# Control_board_FINAL.net
KiCad netlist of a schematic drawn in EAGLE
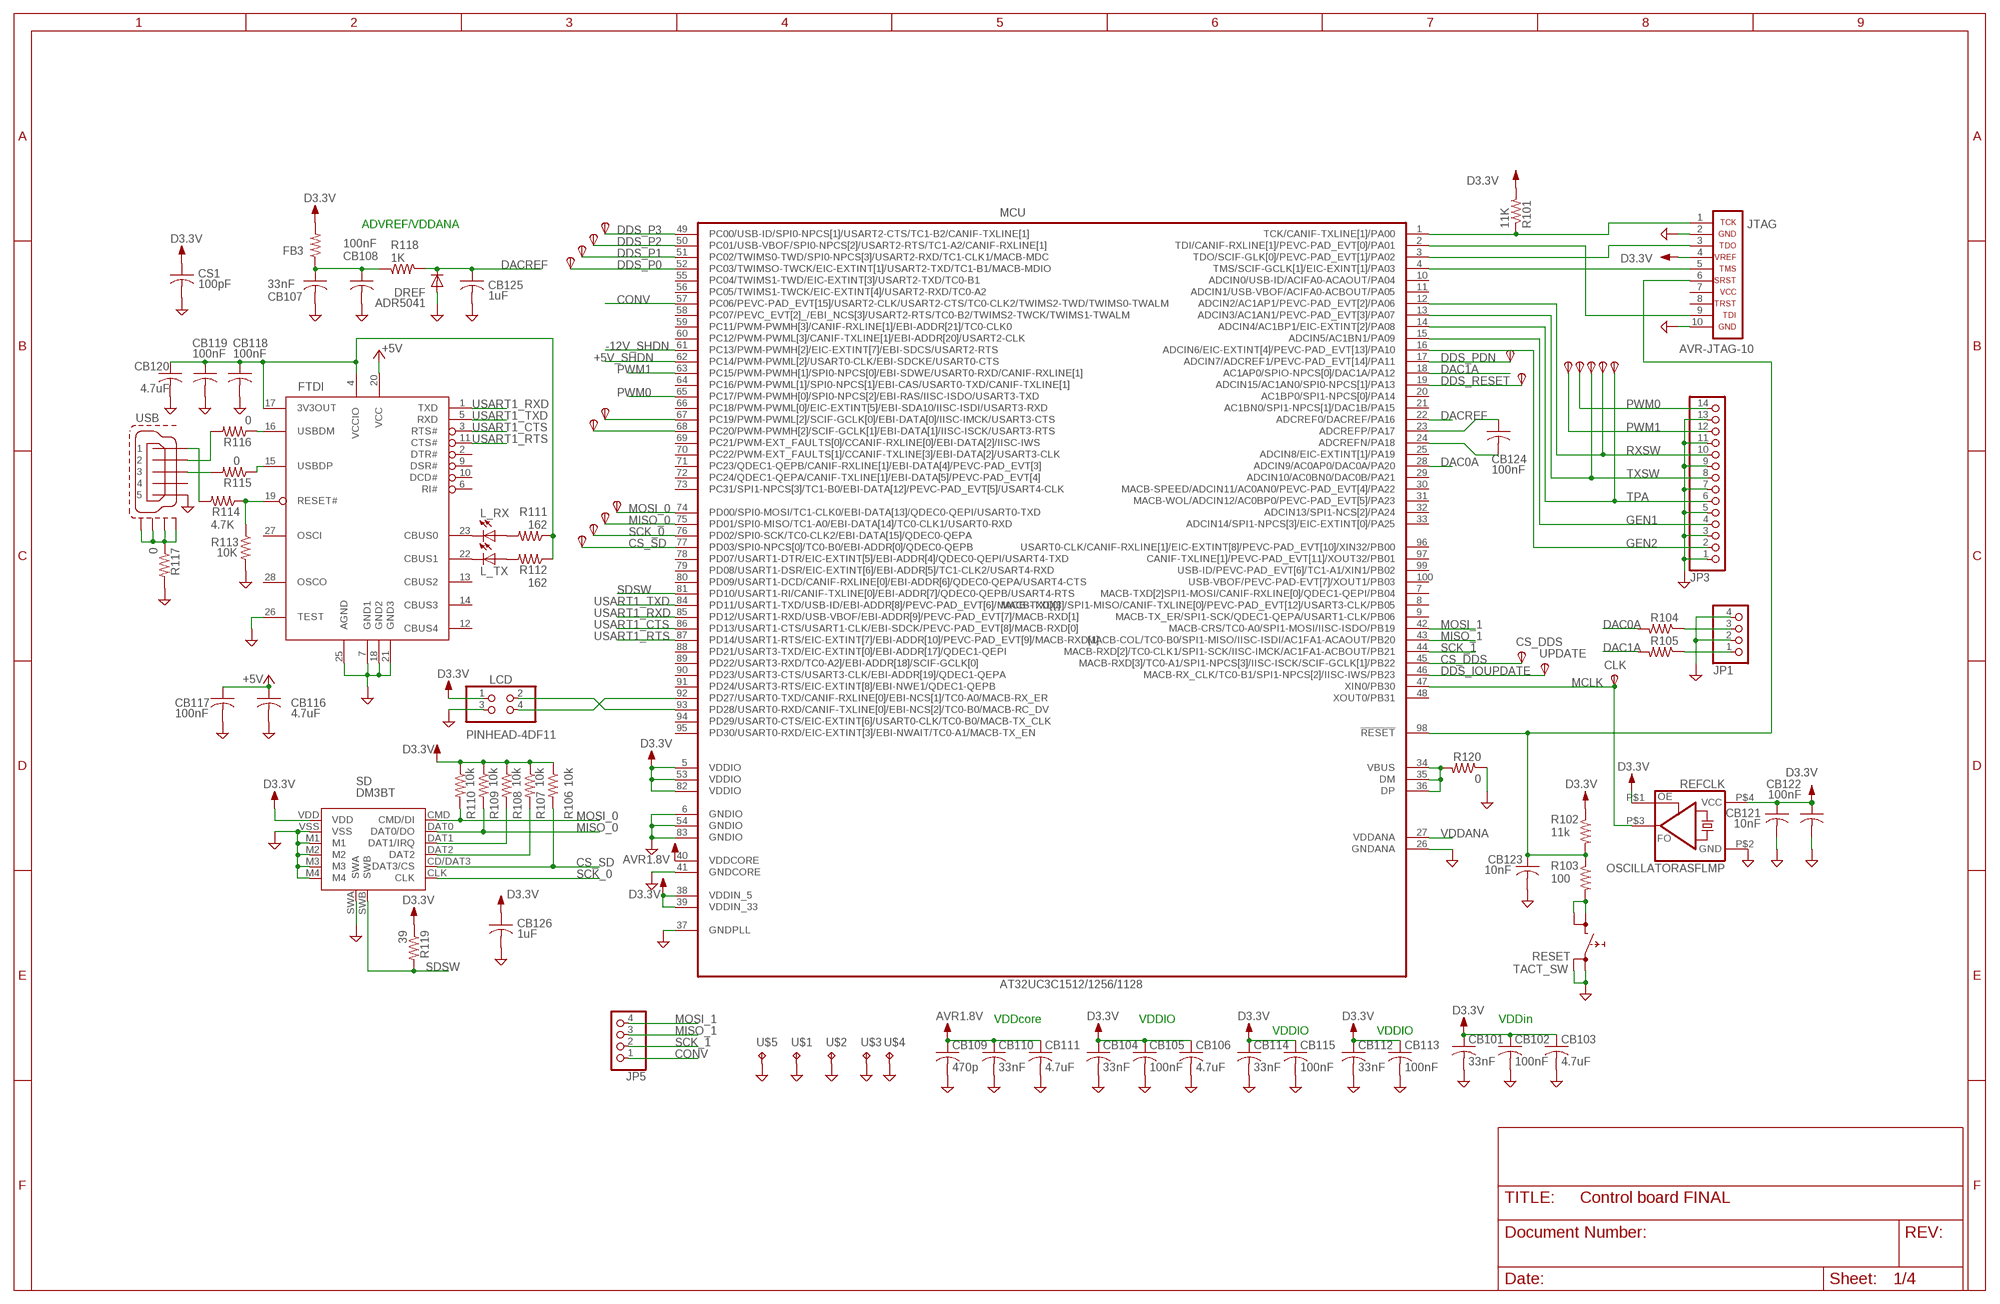
[diagram p0: schematic, sheet 1]
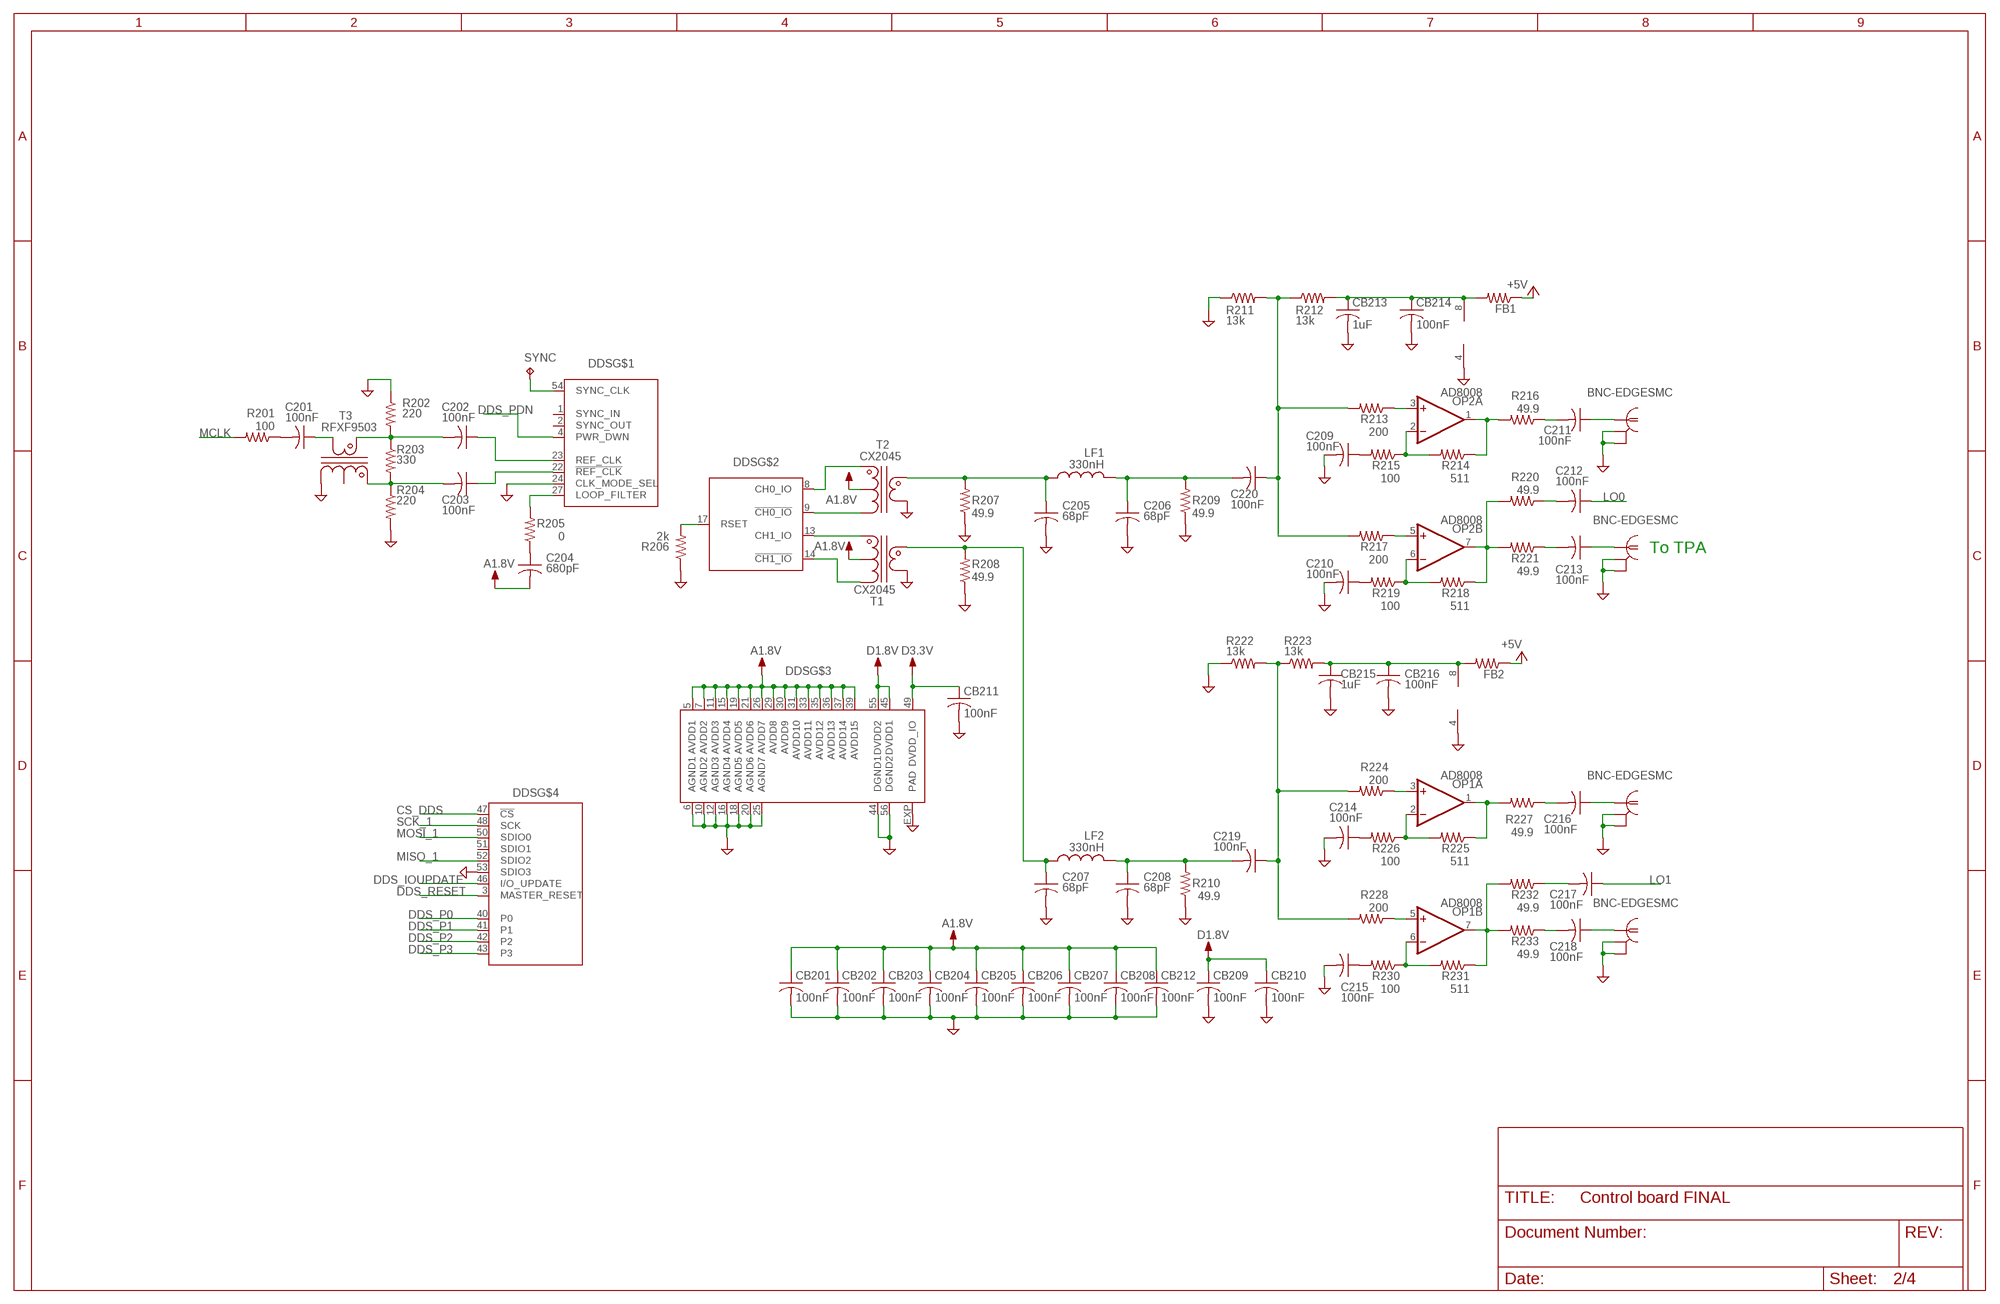
[diagram p1: schematic, sheet 2]
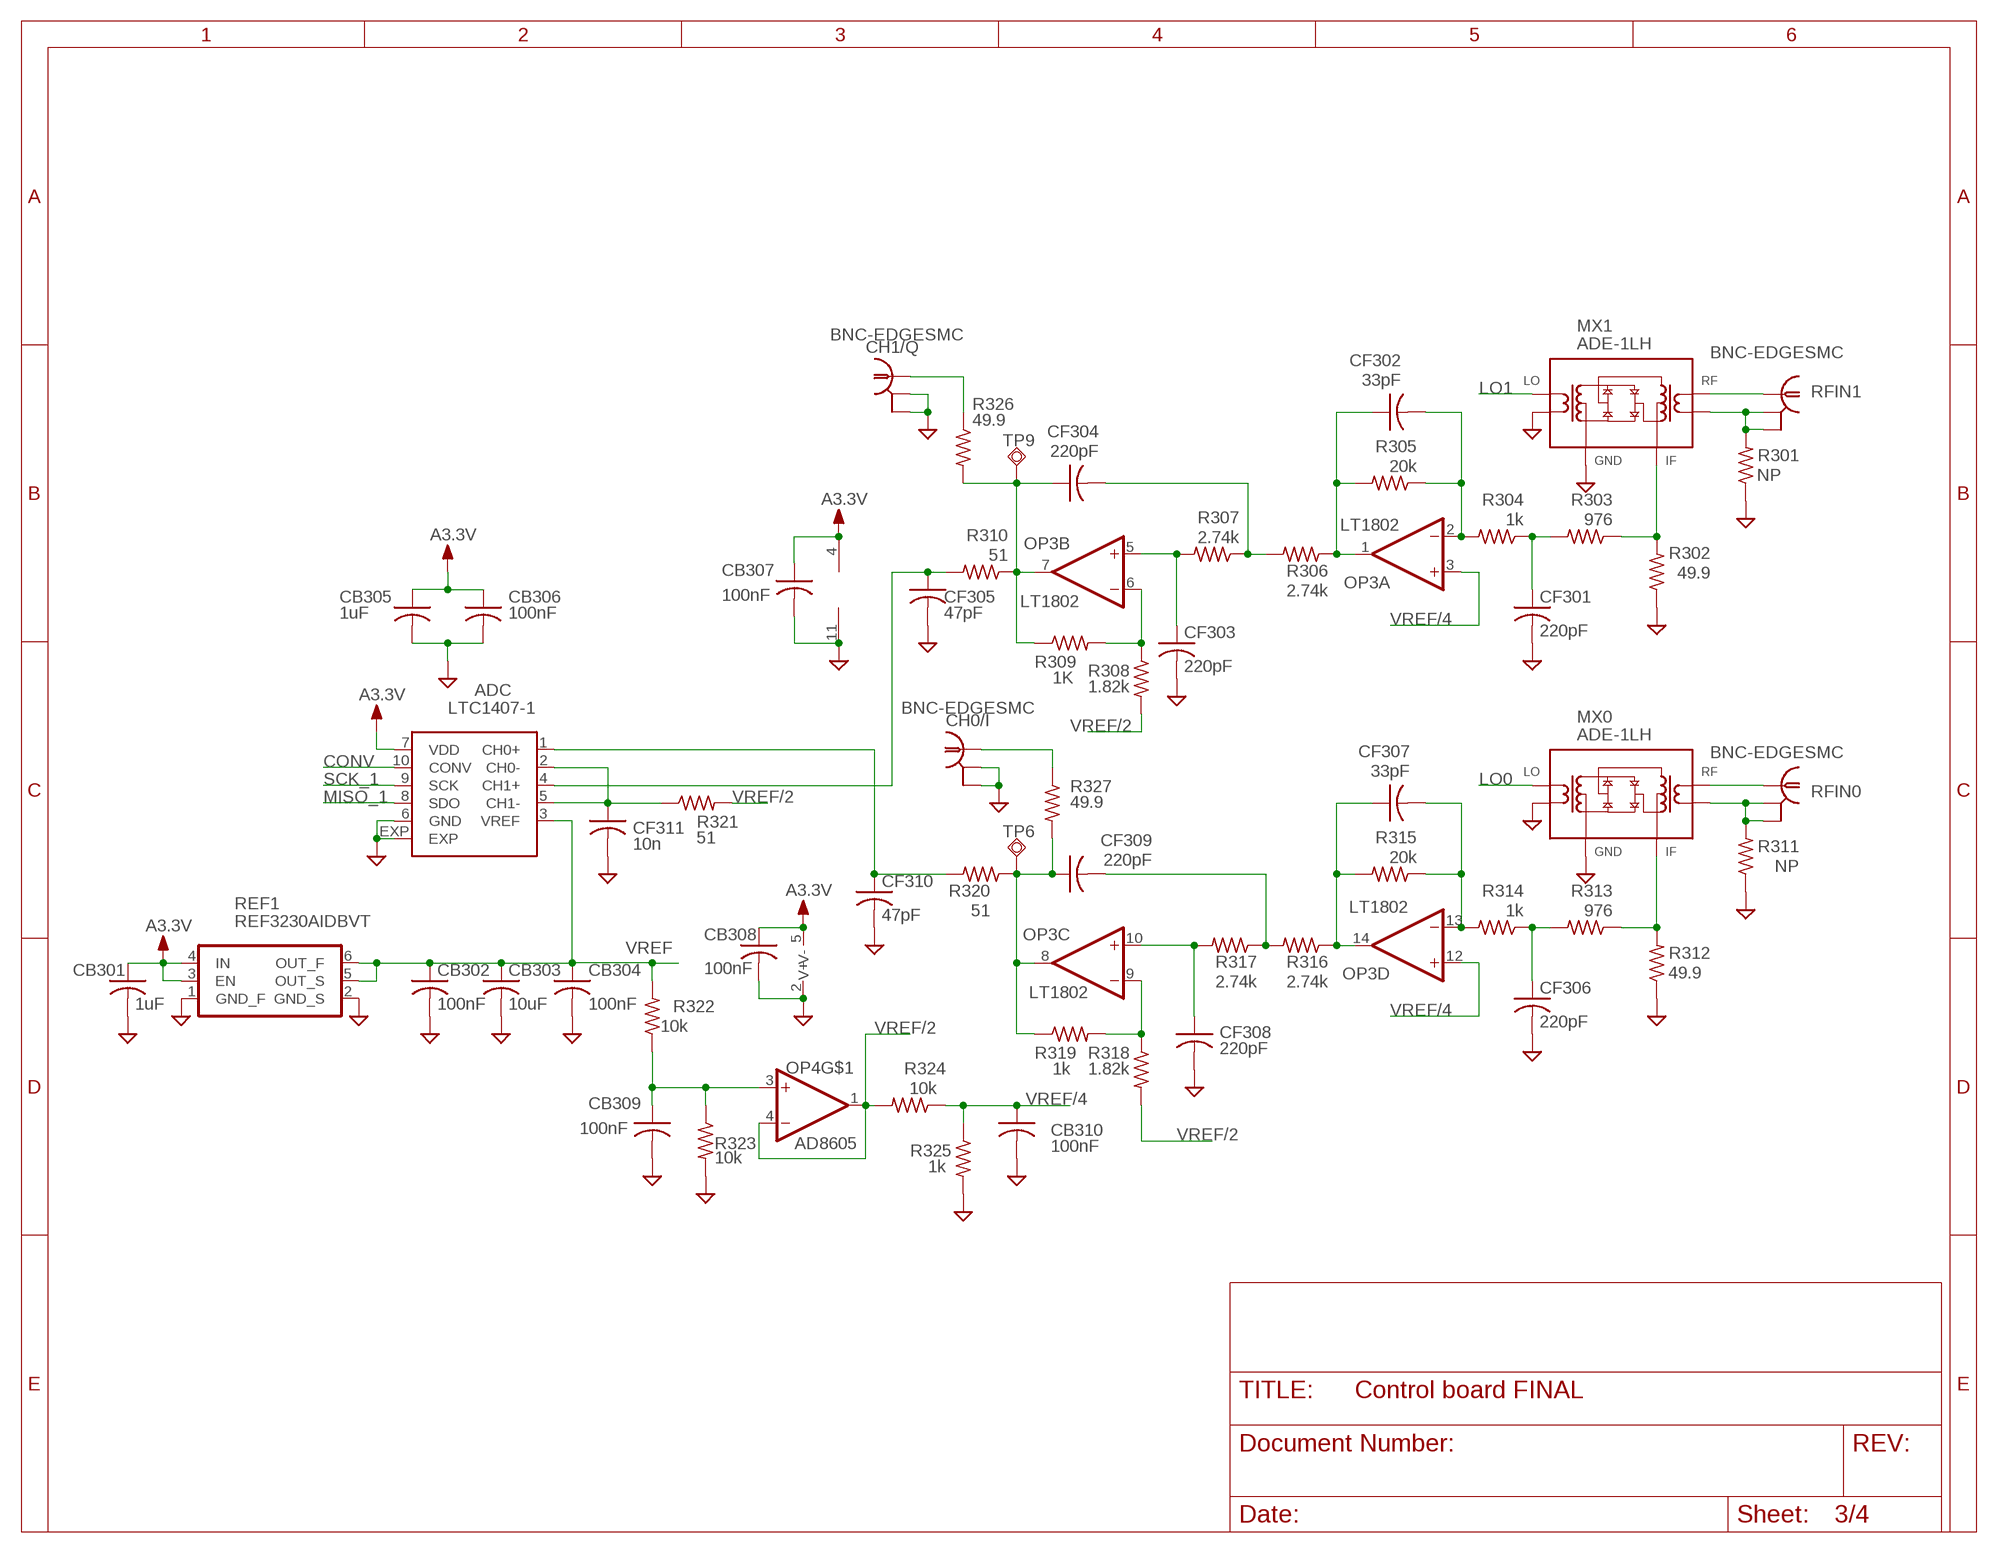
[diagram p2: schematic, sheet 3]
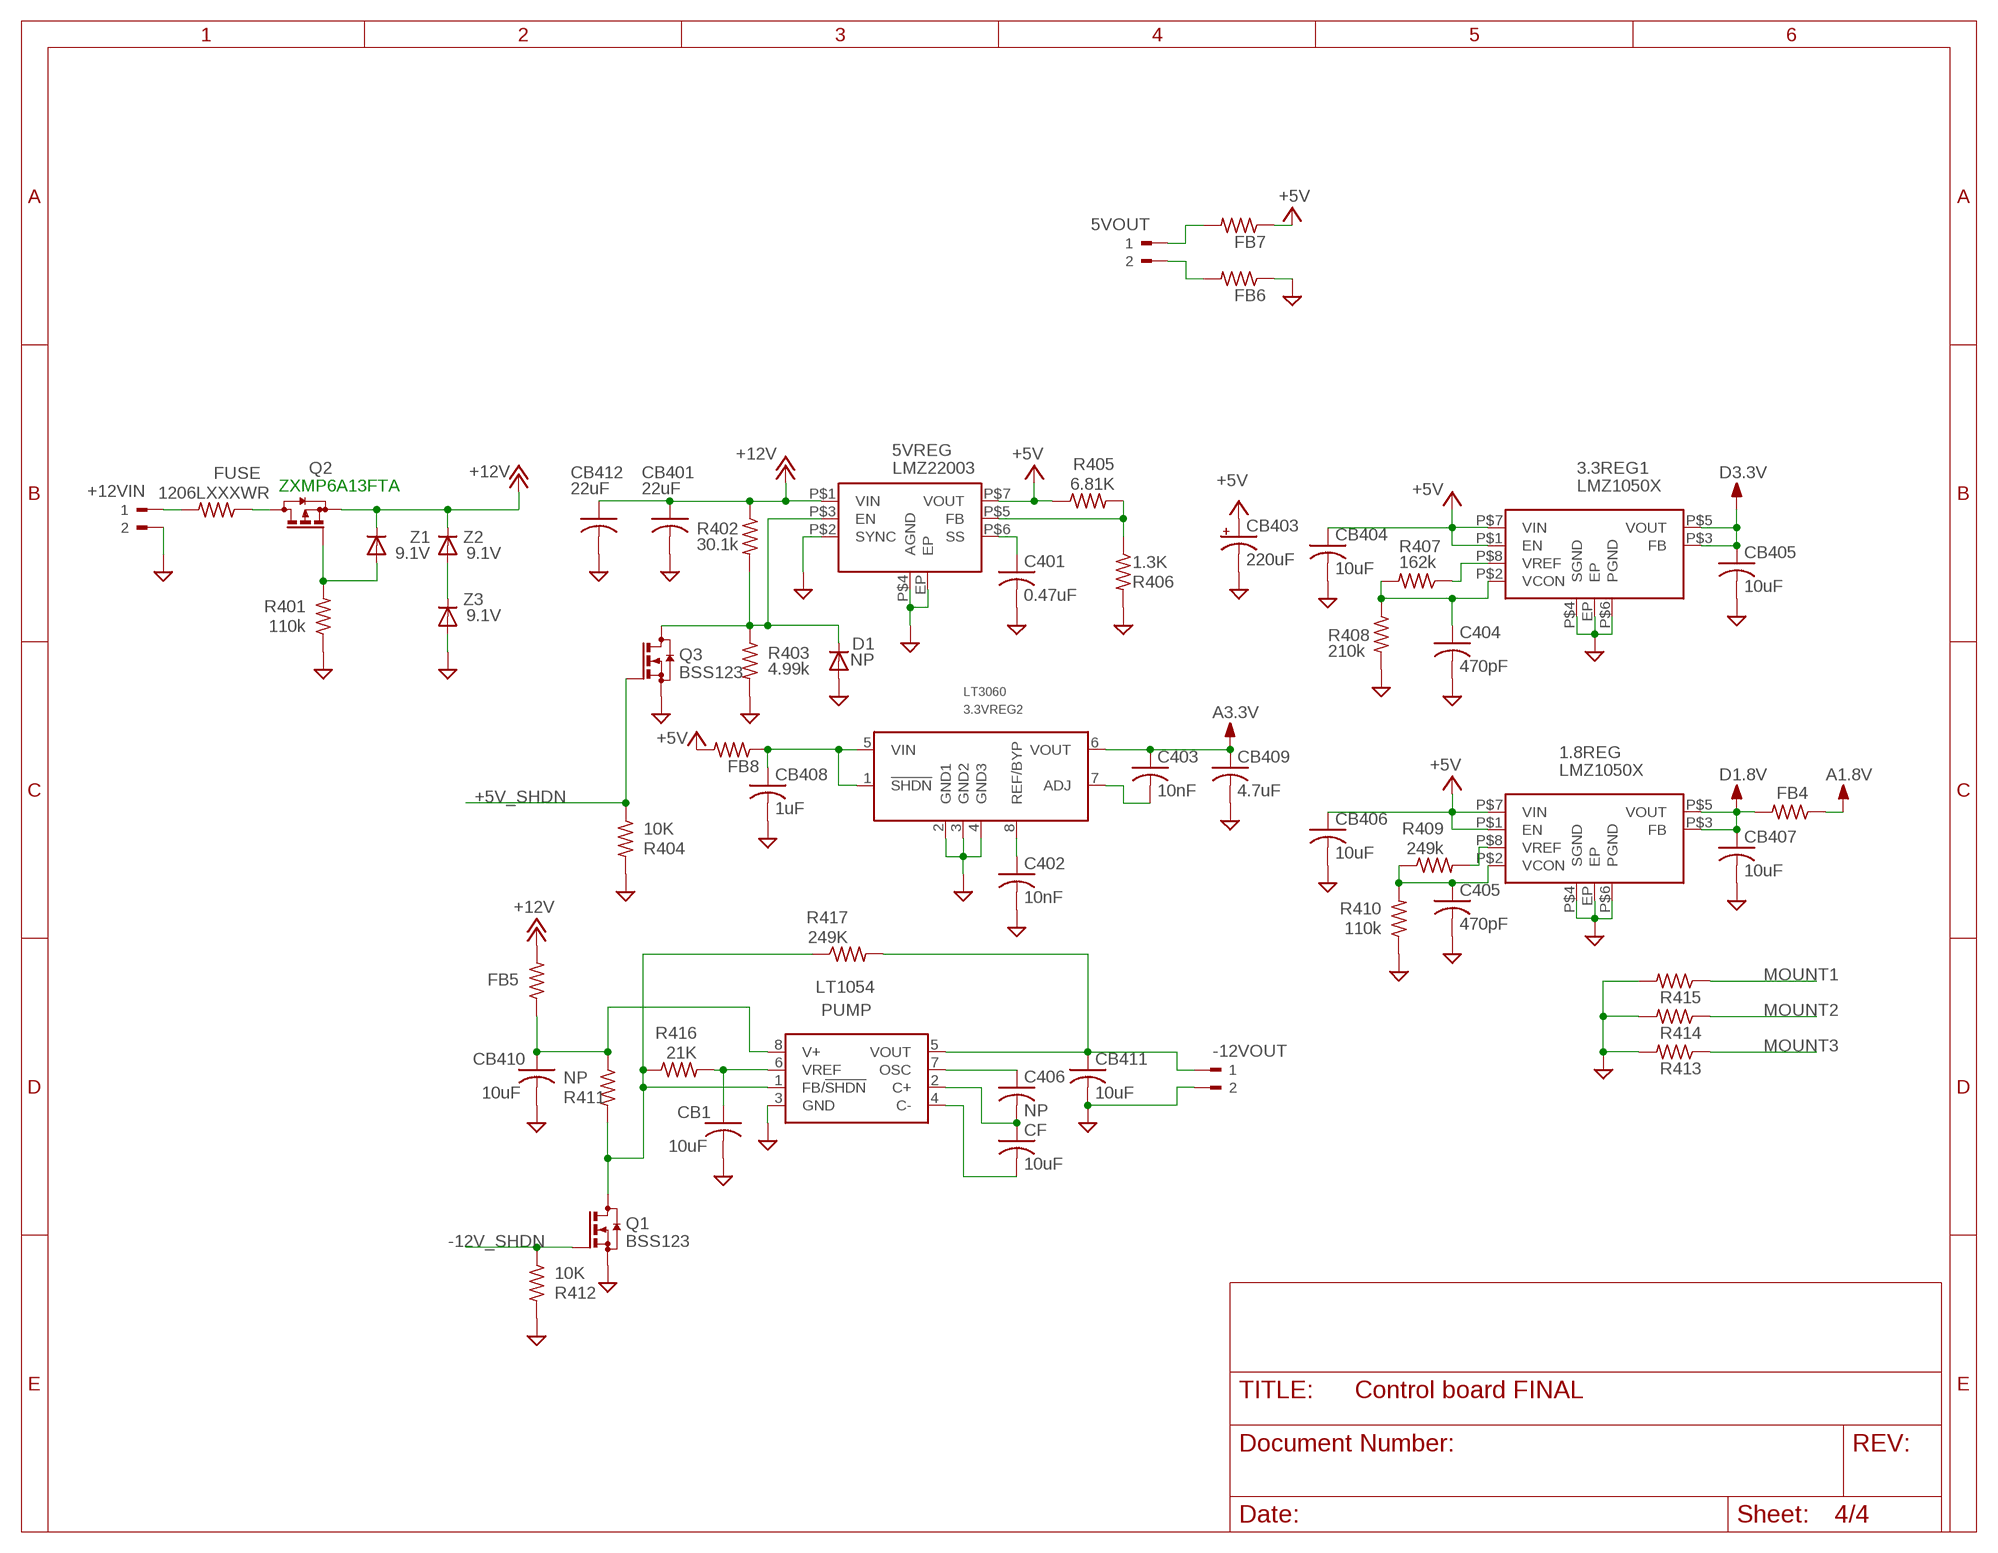
[diagram p3: schematic, sheet 4]

(export (version "E")
  (design (tool "Eeschema 10.0.6"))
  (components
    (comp (ref "CB101")
      (value "33nF")
      (footprint "eagle-import:C0603")
      (libsource (lib "eagle-import") (part "C-USC0603"))
    )
    (comp (ref "CB102")
      (value "100nF")
      (footprint "eagle-import:C0603")
      (libsource (lib "eagle-import") (part "C-USC0603"))
    )
    (comp (ref "CB103")
      (value "4.7uF")
      (footprint "eagle-import:C0805")
      (libsource (lib "eagle-import") (part "C-USC0805"))
    )
    (comp (ref "CB104")
      (value "33nF")
      (footprint "eagle-import:C0603")
      (libsource (lib "eagle-import") (part "C-USC0603"))
    )
    (comp (ref "CB105")
      (value "100nF")
      (footprint "eagle-import:C0603")
      (libsource (lib "eagle-import") (part "C-USC0603"))
    )
    (comp (ref "CB106")
      (value "4.7uF")
      (footprint "eagle-import:C0805")
      (libsource (lib "eagle-import") (part "C-USC0805"))
    )
    (comp (ref "CB107")
      (value "33nF")
      (footprint "eagle-import:C0603")
      (libsource (lib "eagle-import") (part "C-USC0603"))
    )
    (comp (ref "CB108")
      (value "100nF")
      (footprint "eagle-import:C0603")
      (libsource (lib "eagle-import") (part "C-USC0603"))
    )
    (comp (ref "CB109")
      (value "470p")
      (footprint "eagle-import:C0603")
      (libsource (lib "eagle-import") (part "C-USC0603"))
    )
    (comp (ref "CB110")
      (value "33nF")
      (footprint "eagle-import:C0603")
      (libsource (lib "eagle-import") (part "C-USC0603"))
    )
    (comp (ref "CB111")
      (value "4.7uF")
      (footprint "eagle-import:C0805")
      (libsource (lib "eagle-import") (part "C-USC0805"))
    )
    (comp (ref "CB112")
      (value "33nF")
      (footprint "eagle-import:C0603")
      (libsource (lib "eagle-import") (part "C-USC0603"))
    )
    (comp (ref "CB113")
      (value "100nF")
      (footprint "eagle-import:C0603")
      (libsource (lib "eagle-import") (part "C-USC0603"))
    )
    (comp (ref "CB114")
      (value "33nF")
      (footprint "eagle-import:C0603")
      (libsource (lib "eagle-import") (part "C-USC0603"))
    )
    (comp (ref "CB115")
      (value "100nF")
      (footprint "eagle-import:C0603")
      (libsource (lib "eagle-import") (part "C-USC0603"))
    )
    (comp (ref "CB116")
      (value "4.7uF")
      (footprint "eagle-import:C0805")
      (libsource (lib "eagle-import") (part "C-USC0805"))
    )
    (comp (ref "CB117")
      (value "100nF")
      (footprint "eagle-import:C0603")
      (libsource (lib "eagle-import") (part "C-USC0603"))
    )
    (comp (ref "CB118")
      (value "100nF")
      (footprint "eagle-import:C0603")
      (libsource (lib "eagle-import") (part "C-USC0603"))
    )
    (comp (ref "CB119")
      (value "100nF")
      (footprint "eagle-import:C0603")
      (libsource (lib "eagle-import") (part "C-USC0603"))
    )
    (comp (ref "CB120")
      (value "4.7uF")
      (footprint "eagle-import:C0805")
      (libsource (lib "eagle-import") (part "C-USC0805"))
    )
    (comp (ref "CB121")
      (value "10nF")
      (footprint "eagle-import:C0603")
      (libsource (lib "eagle-import") (part "C-USC0603"))
    )
    (comp (ref "CB122")
      (value "100nF")
      (footprint "eagle-import:C0603")
      (libsource (lib "eagle-import") (part "C-USC0603"))
    )
    (comp (ref "CB123")
      (value "10nF")
      (footprint "eagle-import:C0603")
      (libsource (lib "eagle-import") (part "C-USC0603"))
    )
    (comp (ref "CB124")
      (value "100nF")
      (footprint "eagle-import:C0603")
      (libsource (lib "eagle-import") (part "C-USC0603"))
    )
    (comp (ref "CB125")
      (value "1uF")
      (footprint "eagle-import:C0603")
      (libsource (lib "eagle-import") (part "C-USC0603"))
    )
    (comp (ref "CB126")
      (value "1uF")
      (footprint "eagle-import:C0603")
      (libsource (lib "eagle-import") (part "C-USC0603"))
    )
    (comp (ref "CLK")
      (value "TPSTP10R")
      (footprint "eagle-import:TP10R")
      (libsource (lib "eagle-import") (part "TPSTP10R"))
    )
    (comp (ref "CS1")
      (value "100pF")
      (footprint "eagle-import:C0805")
      (libsource (lib "eagle-import") (part "C-USC0805"))
    )
    (comp (ref "CS_DDS")
      (value "TPSTP10R")
      (footprint "eagle-import:TP10R")
      (libsource (lib "eagle-import") (part "TPSTP10R"))
    )
    (comp (ref "CS_SD")
      (value "TPSTP10R")
      (footprint "eagle-import:TP10R")
      (libsource (lib "eagle-import") (part "TPSTP10R"))
    )
    (comp (ref "DDSPDN")
      (value "TPSTP10R")
      (footprint "eagle-import:TP10R")
      (libsource (lib "eagle-import") (part "TPSTP10R"))
    )
    (comp (ref "DDSRESET")
      (value "TPSTP10R")
      (footprint "eagle-import:TP10R")
      (libsource (lib "eagle-import") (part "TPSTP10R"))
    )
    (comp (ref "DREF")
      (value "ADR5041")
      (footprint "eagle-import:SOT23-3")
      (libsource (lib "eagle-import") (part "REFERENCE-ADR50XXSOT23-3"))
    )
    (comp (ref "FB3")
      (value "R-US_R0603")
      (footprint "eagle-import:R0603")
      (libsource (lib "eagle-import") (part "resistor_R-US_R0603"))
    )
    (comp (ref "FTDI")
      (value "FT232RL")
      (footprint "eagle-import:SSOP28DB")
      (libsource (lib "eagle-import") (part "FT232RL"))
    )
    (comp (ref "GCLK0")
      (value "TPSTP10R")
      (footprint "eagle-import:TP10R")
      (libsource (lib "eagle-import") (part "TPSTP10R"))
    )
    (comp (ref "GCLK1")
      (value "TPSTP10R")
      (footprint "eagle-import:TP10R")
      (libsource (lib "eagle-import") (part "TPSTP10R"))
    )
    (comp (ref "JP1")
      (value "PINHD-1X4")
      (footprint "eagle-import:1X04")
      (libsource (lib "eagle-import") (part "PINHD-1X4"))
    )
    (comp (ref "JP3")
      (value "PINHD-1X14")
      (footprint "eagle-import:1X14")
      (libsource (lib "eagle-import") (part "PINHD-1X14"))
    )
    (comp (ref "JP5")
      (value "PINHD-1X4")
      (footprint "eagle-import:1X04")
      (libsource (lib "eagle-import") (part "PINHD-1X4"))
    )
    (comp (ref "JTAG")
      (value "AVR-JTAG-10")
      (footprint "eagle-import:AVR-JTAG-10")
      (libsource (lib "eagle-import") (part "AVR-JTAG-10"))
    )
    (comp (ref "LCD")
      (value "PINHEAD-4DF11")
      (footprint "eagle-import:DF11-4POS")
      (libsource (lib "eagle-import") (part "PINHEAD-4DF11"))
    )
    (comp (ref "L_RX")
      (value "LEDCHIPLED_0805")
      (footprint "eagle-import:CHIPLED_0805")
      (libsource (lib "eagle-import") (part "LEDCHIPLED_0805"))
    )
    (comp (ref "L_TX")
      (value "LEDCHIPLED_0805")
      (footprint "eagle-import:CHIPLED_0805")
      (libsource (lib "eagle-import") (part "LEDCHIPLED_0805"))
    )
    (comp (ref "MCU")
      (value "AT32UC3C1512/1256/1128")
      (footprint "eagle-import:TQFP100")
      (libsource (lib "eagle-import") (part "AT32UC3C1512/1256/1128"))
    )
    (comp (ref "MISO0")
      (value "TPSTP10R")
      (footprint "eagle-import:TP10R")
      (libsource (lib "eagle-import") (part "TPSTP10R"))
    )
    (comp (ref "MOSI0")
      (value "TPSTP10R")
      (footprint "eagle-import:TP10R")
      (libsource (lib "eagle-import") (part "TPSTP10R"))
    )
    (comp (ref "P0")
      (value "TPSTP10R")
      (footprint "eagle-import:TP10R")
      (libsource (lib "eagle-import") (part "TPSTP10R"))
    )
    (comp (ref "P1")
      (value "TPSTP10R")
      (footprint "eagle-import:TP10R")
      (libsource (lib "eagle-import") (part "TPSTP10R"))
    )
    (comp (ref "P2")
      (value "TPSTP10R")
      (footprint "eagle-import:TP10R")
      (libsource (lib "eagle-import") (part "TPSTP10R"))
    )
    (comp (ref "P3")
      (value "TPSTP10R")
      (footprint "eagle-import:TP10R")
      (libsource (lib "eagle-import") (part "TPSTP10R"))
    )
    (comp (ref "R101")
      (value "11K")
      (footprint "eagle-import:R0805")
      (libsource (lib "eagle-import") (part "R-US_R0805"))
    )
    (comp (ref "R102")
      (value "11k")
      (footprint "eagle-import:R0805")
      (libsource (lib "eagle-import") (part "R-US_R0805"))
    )
    (comp (ref "R103")
      (value "100")
      (footprint "eagle-import:R0805")
      (libsource (lib "eagle-import") (part "R-US_R0805"))
    )
    (comp (ref "R104")
      (value "R-US_R0805")
      (footprint "eagle-import:R0805")
      (libsource (lib "eagle-import") (part "R-US_R0805"))
    )
    (comp (ref "R105")
      (value "R-US_R0805")
      (footprint "eagle-import:R0805")
      (libsource (lib "eagle-import") (part "R-US_R0805"))
    )
    (comp (ref "R106")
      (value "10k")
      (footprint "eagle-import:R0805")
      (libsource (lib "eagle-import") (part "R-US_R0805"))
    )
    (comp (ref "R107")
      (value "10k")
      (footprint "eagle-import:R0805")
      (libsource (lib "eagle-import") (part "R-US_R0805"))
    )
    (comp (ref "R108")
      (value "10k")
      (footprint "eagle-import:R0805")
      (libsource (lib "eagle-import") (part "R-US_R0805"))
    )
    (comp (ref "R109")
      (value "10k")
      (footprint "eagle-import:R0805")
      (libsource (lib "eagle-import") (part "R-US_R0805"))
    )
    (comp (ref "R110")
      (value "10k")
      (footprint "eagle-import:R0805")
      (libsource (lib "eagle-import") (part "R-US_R0805"))
    )
    (comp (ref "R111")
      (value "162")
      (footprint "eagle-import:R0805")
      (libsource (lib "eagle-import") (part "R-US_R0805"))
    )
    (comp (ref "R112")
      (value "162")
      (footprint "eagle-import:R0805")
      (libsource (lib "eagle-import") (part "R-US_R0805"))
    )
    (comp (ref "R113")
      (value "10K")
      (footprint "eagle-import:R0805")
      (libsource (lib "eagle-import") (part "R-US_R0805"))
    )
    (comp (ref "R114")
      (value "4.7K")
      (footprint "eagle-import:R0805")
      (libsource (lib "eagle-import") (part "R-US_R0805"))
    )
    (comp (ref "R115")
      (value "0")
      (footprint "eagle-import:R0805")
      (libsource (lib "eagle-import") (part "R-US_R0805"))
    )
    (comp (ref "R116")
      (value "0")
      (footprint "eagle-import:R0805")
      (libsource (lib "eagle-import") (part "R-US_R0805"))
    )
    (comp (ref "R117")
      (value "0")
      (footprint "eagle-import:R0805")
      (libsource (lib "eagle-import") (part "R-US_R0805"))
    )
    (comp (ref "R118")
      (value "1K")
      (footprint "eagle-import:R0805")
      (libsource (lib "eagle-import") (part "R-US_R0805"))
    )
    (comp (ref "R119")
      (value "39")
      (footprint "eagle-import:R0805")
      (libsource (lib "eagle-import") (part "R-US_R0805"))
    )
    (comp (ref "R120")
      (value "0")
      (footprint "eagle-import:R0805")
      (libsource (lib "eagle-import") (part "R-US_R0805"))
    )
    (comp (ref "REFCLK")
      (value "OSCILLATORASFLMP")
      (footprint "eagle-import:QFN4_ASFLMP_OSCILLATOR")
      (libsource (lib "eagle-import") (part "OSCILLATORASFLMP"))
    )
    (comp (ref "RESET")
      (value "TACT_SW")
      (footprint "eagle-import:KMR2_TACT_SWITCH")
      (libsource (lib "eagle-import") (part "TACT_SW"))
    )
    (comp (ref "SCK0")
      (value "TPSTP10R")
      (footprint "eagle-import:TP10R")
      (libsource (lib "eagle-import") (part "TPSTP10R"))
    )
    (comp (ref "SD")
      (value "DM3BT")
      (footprint "eagle-import:DM3BT")
      (libsource (lib "eagle-import") (part "DM3BT"))
    )
    (comp (ref "TP1")
      (value "TPSTP10R")
      (footprint "eagle-import:TP10R")
      (libsource (lib "eagle-import") (part "TPSTP10R"))
    )
    (comp (ref "TP2")
      (value "TPSTP10R")
      (footprint "eagle-import:TP10R")
      (libsource (lib "eagle-import") (part "TPSTP10R"))
    )
    (comp (ref "TP3")
      (value "TPSTP10R")
      (footprint "eagle-import:TP10R")
      (libsource (lib "eagle-import") (part "TPSTP10R"))
    )
    (comp (ref "TP4")
      (value "TPSTP10R")
      (footprint "eagle-import:TP10R")
      (libsource (lib "eagle-import") (part "TPSTP10R"))
    )
    (comp (ref "TP5")
      (value "TPSTP10R")
      (footprint "eagle-import:TP10R")
      (libsource (lib "eagle-import") (part "TPSTP10R"))
    )
    (comp (ref "U$1")
      (value "TESTPOINTKEYSTONE_ELECTRONICS_5016")
      (footprint "eagle-import:SMD_TESTPAD")
      (libsource (lib "eagle-import") (part "TESTPOINTKEYSTONE_ELECTRONICS_5016"))
    )
    (comp (ref "U$2")
      (value "TESTPOINTKEYSTONE_ELECTRONICS_5016")
      (footprint "eagle-import:SMD_TESTPAD")
      (libsource (lib "eagle-import") (part "TESTPOINTKEYSTONE_ELECTRONICS_5016"))
    )
    (comp (ref "U$3")
      (value "TESTPOINTKEYSTONE_ELECTRONICS_5016")
      (footprint "eagle-import:SMD_TESTPAD")
      (libsource (lib "eagle-import") (part "TESTPOINTKEYSTONE_ELECTRONICS_5016"))
    )
    (comp (ref "U$4")
      (value "TESTPOINTKEYSTONE_ELECTRONICS_5016")
      (footprint "eagle-import:SMD_TESTPAD")
      (libsource (lib "eagle-import") (part "TESTPOINTKEYSTONE_ELECTRONICS_5016"))
    )
    (comp (ref "U$5")
      (value "TESTPOINTKEYSTONE_ELECTRONICS_5016")
      (footprint "eagle-import:SMD_TESTPAD")
      (libsource (lib "eagle-import") (part "TESTPOINTKEYSTONE_ELECTRONICS_5016"))
    )
    (comp (ref "UPDATE")
      (value "TPSTP10R")
      (footprint "eagle-import:TP10R")
      (libsource (lib "eagle-import") (part "TPSTP10R"))
    )
    (comp (ref "USB")
      (value "MINI-USB-SHIELD-UX60A-MB-5ST")
      (footprint "eagle-import:UX60A-MB-5ST")
      (libsource (lib "eagle-import") (part "MINI-USB-SHIELD-UX60A-MB-5ST"))
    )
    (comp (ref "ADC")
      (value "LTC1407-1")
      (footprint "eagle-import:MSOP-10-EXP")
      (libsource (lib "eagle-import") (part "LTC1407-1"))
    )
    (comp (ref "CB301")
      (value "1uF")
      (footprint "eagle-import:C0603")
      (libsource (lib "eagle-import") (part "C-USC0603"))
    )
    (comp (ref "CB302")
      (value "100nF")
      (footprint "eagle-import:C0603")
      (libsource (lib "eagle-import") (part "C-USC0603"))
    )
    (comp (ref "CB303")
      (value "10uF")
      (footprint "eagle-import:C0805")
      (libsource (lib "eagle-import") (part "C-USC0805"))
    )
    (comp (ref "CB304")
      (value "100nF")
      (footprint "eagle-import:C0603")
      (libsource (lib "eagle-import") (part "C-USC0603"))
    )
    (comp (ref "CB305")
      (value "1uF")
      (footprint "eagle-import:C0603")
      (libsource (lib "eagle-import") (part "C-USC0603"))
    )
    (comp (ref "CB306")
      (value "100nF")
      (footprint "eagle-import:C0603")
      (libsource (lib "eagle-import") (part "C-USC0603"))
    )
    (comp (ref "CB307")
      (value "100nF")
      (footprint "eagle-import:C0603")
      (libsource (lib "eagle-import") (part "C-USC0603"))
    )
    (comp (ref "CB308")
      (value "100nF")
      (footprint "eagle-import:C0603")
      (libsource (lib "eagle-import") (part "C-USC0603"))
    )
    (comp (ref "CB309")
      (value "100nF")
      (footprint "eagle-import:C0603")
      (libsource (lib "eagle-import") (part "C-USC0603"))
    )
    (comp (ref "CB310")
      (value "100nF")
      (footprint "eagle-import:C0603")
      (libsource (lib "eagle-import") (part "C-USC0603"))
    )
    (comp (ref "CF301")
      (value "220pF")
      (footprint "eagle-import:C0805")
      (libsource (lib "eagle-import") (part "C-USC0805"))
    )
    (comp (ref "CF302")
      (value "33pF")
      (footprint "eagle-import:C0805")
      (libsource (lib "eagle-import") (part "C-USC0805"))
    )
    (comp (ref "CF303")
      (value "220pF")
      (footprint "eagle-import:C0805")
      (libsource (lib "eagle-import") (part "C-USC0805"))
    )
    (comp (ref "CF304")
      (value "220pF")
      (footprint "eagle-import:C0805")
      (libsource (lib "eagle-import") (part "C-USC0805"))
    )
    (comp (ref "CF305")
      (value "47pF")
      (footprint "eagle-import:C0603")
      (libsource (lib "eagle-import") (part "C-USC0603"))
    )
    (comp (ref "CF306")
      (value "220pF")
      (footprint "eagle-import:C0805")
      (libsource (lib "eagle-import") (part "C-USC0805"))
    )
    (comp (ref "CF307")
      (value "33pF")
      (footprint "eagle-import:C0805")
      (libsource (lib "eagle-import") (part "C-USC0805"))
    )
    (comp (ref "CF308")
      (value "220pF")
      (footprint "eagle-import:C0805")
      (libsource (lib "eagle-import") (part "C-USC0805"))
    )
    (comp (ref "CF309")
      (value "220pF")
      (footprint "eagle-import:C0805")
      (libsource (lib "eagle-import") (part "C-USC0805"))
    )
    (comp (ref "CF310")
      (value "47pF")
      (footprint "eagle-import:C0603")
      (libsource (lib "eagle-import") (part "C-USC0603"))
    )
    (comp (ref "CF311")
      (value "10n")
      (footprint "eagle-import:C0603")
      (libsource (lib "eagle-import") (part "C-USC0603"))
    )
    (comp (ref "CH0/I")
      (value "BNC-EDGESMC")
      (footprint "eagle-import:SMC-EDGE")
      (libsource (lib "eagle-import") (part "BNC-EDGESMC"))
    )
    (comp (ref "CH1/Q")
      (value "BNC-EDGESMC")
      (footprint "eagle-import:SMC-EDGE")
      (libsource (lib "eagle-import") (part "BNC-EDGESMC"))
    )
    (comp (ref "MX0")
      (value "ADE-1LH")
      (footprint "eagle-import:CD636")
      (libsource (lib "eagle-import") (part "ADE-1LH"))
    )
    (comp (ref "MX1")
      (value "ADE-1LH")
      (footprint "eagle-import:CD636")
      (libsource (lib "eagle-import") (part "ADE-1LH"))
    )
    (comp (ref "OP3")
      (value "LT1802")
      (footprint "eagle-import:SO14")
      (libsource (lib "eagle-import") (part "4AMP_P4+11D"))
    )
    (comp (ref "OP4")
      (value "AD8605")
      (footprint "eagle-import:SOT23-5")
      (libsource (lib "eagle-import") (part "LMH6624"))
    )
    (comp (ref "R301")
      (value "NP")
      (footprint "eagle-import:R0805")
      (libsource (lib "eagle-import") (part "R-US_R0805"))
    )
    (comp (ref "R302")
      (value "49.9")
      (footprint "eagle-import:R0805")
      (libsource (lib "eagle-import") (part "R-US_R0805"))
    )
    (comp (ref "R303")
      (value "976")
      (footprint "eagle-import:R0805")
      (libsource (lib "eagle-import") (part "R-US_R0805"))
    )
    (comp (ref "R304")
      (value "1k")
      (footprint "eagle-import:R0805")
      (libsource (lib "eagle-import") (part "R-US_R0805"))
    )
    (comp (ref "R305")
      (value "20k")
      (footprint "eagle-import:R0805")
      (libsource (lib "eagle-import") (part "R-US_R0805"))
    )
    (comp (ref "R306")
      (value "2.74k")
      (footprint "eagle-import:R0805")
      (libsource (lib "eagle-import") (part "R-US_R0805"))
    )
    (comp (ref "R307")
      (value "2.74k")
      (footprint "eagle-import:R0805")
      (libsource (lib "eagle-import") (part "R-US_R0805"))
    )
    (comp (ref "R308")
      (value "1.82k")
      (footprint "eagle-import:R0805")
      (libsource (lib "eagle-import") (part "R-US_R0805"))
    )
    (comp (ref "R309")
      (value "1K")
      (footprint "eagle-import:R0805")
      (libsource (lib "eagle-import") (part "R-US_R0805"))
    )
    (comp (ref "R310")
      (value "51")
      (footprint "eagle-import:R0805")
      (libsource (lib "eagle-import") (part "R-US_R0805"))
    )
    (comp (ref "R311")
      (value "NP")
      (footprint "eagle-import:R0805")
      (libsource (lib "eagle-import") (part "R-US_R0805"))
    )
    (comp (ref "R312")
      (value "49.9")
      (footprint "eagle-import:R0805")
      (libsource (lib "eagle-import") (part "R-US_R0805"))
    )
    (comp (ref "R313")
      (value "976")
      (footprint "eagle-import:R0805")
      (libsource (lib "eagle-import") (part "R-US_R0805"))
    )
    (comp (ref "R314")
      (value "1k")
      (footprint "eagle-import:R0805")
      (libsource (lib "eagle-import") (part "R-US_R0805"))
    )
    (comp (ref "R315")
      (value "20k")
      (footprint "eagle-import:R0805")
      (libsource (lib "eagle-import") (part "R-US_R0805"))
    )
    (comp (ref "R316")
      (value "2.74k")
      (footprint "eagle-import:R0805")
      (libsource (lib "eagle-import") (part "R-US_R0805"))
    )
    (comp (ref "R317")
      (value "2.74k")
      (footprint "eagle-import:R0805")
      (libsource (lib "eagle-import") (part "R-US_R0805"))
    )
    (comp (ref "R318")
      (value "1.82k")
      (footprint "eagle-import:R0805")
      (libsource (lib "eagle-import") (part "R-US_R0805"))
    )
    (comp (ref "R319")
      (value "1k")
      (footprint "eagle-import:R0805")
      (libsource (lib "eagle-import") (part "R-US_R0805"))
    )
    (comp (ref "R320")
      (value "51")
      (footprint "eagle-import:R0805")
      (libsource (lib "eagle-import") (part "R-US_R0805"))
    )
    (comp (ref "R321")
      (value "51")
      (footprint "eagle-import:R0805")
      (libsource (lib "eagle-import") (part "R-US_R0805"))
    )
    (comp (ref "R322")
      (value "10k")
      (footprint "eagle-import:R0805")
      (libsource (lib "eagle-import") (part "R-US_R0805"))
    )
    (comp (ref "R323")
      (value "10k")
      (footprint "eagle-import:R0805")
      (libsource (lib "eagle-import") (part "R-US_R0805"))
    )
    (comp (ref "R324")
      (value "10k")
      (footprint "eagle-import:R0805")
      (libsource (lib "eagle-import") (part "R-US_R0805"))
    )
    (comp (ref "R325")
      (value "1k")
      (footprint "eagle-import:R0805")
      (libsource (lib "eagle-import") (part "R-US_R0805"))
    )
    (comp (ref "R326")
      (value "49.9")
      (footprint "eagle-import:R0805")
      (libsource (lib "eagle-import") (part "R-US_R0805"))
    )
    (comp (ref "R327")
      (value "49.9")
      (footprint "eagle-import:R0805")
      (libsource (lib "eagle-import") (part "R-US_R0805"))
    )
    (comp (ref "REF1")
      (value "REF3230AIDBVT")
      (footprint "eagle-import:SOT23-6")
      (libsource (lib "eagle-import") (part "REF32XX"))
    )
    (comp (ref "RFIN0")
      (value "BNC-EDGESMC")
      (footprint "eagle-import:SMC-EDGE")
      (libsource (lib "eagle-import") (part "BNC-EDGESMC"))
    )
    (comp (ref "RFIN1")
      (value "BNC-EDGESMC")
      (footprint "eagle-import:SMC-EDGE")
      (libsource (lib "eagle-import") (part "BNC-EDGESMC"))
    )
    (comp (ref "TP6")
      (value "TPSQTP16R")
      (footprint "eagle-import:TP16R")
      (libsource (lib "eagle-import") (part "TPSQTP16R"))
    )
    (comp (ref "TP9")
      (value "TPSQTP16R")
      (footprint "eagle-import:TP16R")
      (libsource (lib "eagle-import") (part "TPSQTP16R"))
    )
    (comp (ref "C201")
      (value "100nF")
      (footprint "eagle-import:C0603")
      (libsource (lib "eagle-import") (part "C-USC0603"))
    )
    (comp (ref "C202")
      (value "100nF")
      (footprint "eagle-import:C0603")
      (libsource (lib "eagle-import") (part "C-USC0603"))
    )
    (comp (ref "C203")
      (value "100nF")
      (footprint "eagle-import:C0603")
      (libsource (lib "eagle-import") (part "C-USC0603"))
    )
    (comp (ref "C204")
      (value "680pF")
      (footprint "eagle-import:C0805")
      (libsource (lib "eagle-import") (part "C-USC0805"))
    )
    (comp (ref "C205")
      (value "68pF")
      (footprint "eagle-import:1008")
      (libsource (lib "eagle-import") (part "CAPACITOR1008"))
    )
    (comp (ref "C206")
      (value "68pF")
      (footprint "eagle-import:1008")
      (libsource (lib "eagle-import") (part "CAPACITOR1008"))
    )
    (comp (ref "C207")
      (value "68pF")
      (footprint "eagle-import:1008")
      (libsource (lib "eagle-import") (part "CAPACITOR1008"))
    )
    (comp (ref "C208")
      (value "68pF")
      (footprint "eagle-import:1008")
      (libsource (lib "eagle-import") (part "CAPACITOR1008"))
    )
    (comp (ref "C209")
      (value "100nF")
      (footprint "eagle-import:C0603")
      (libsource (lib "eagle-import") (part "C-USC0603"))
    )
    (comp (ref "C210")
      (value "100nF")
      (footprint "eagle-import:C0603")
      (libsource (lib "eagle-import") (part "C-USC0603"))
    )
    (comp (ref "C211")
      (value "100nF")
      (footprint "eagle-import:C0603")
      (libsource (lib "eagle-import") (part "C-USC0603"))
    )
    (comp (ref "C212")
      (value "100nF")
      (footprint "eagle-import:C0603")
      (libsource (lib "eagle-import") (part "C-USC0603"))
    )
    (comp (ref "C213")
      (value "100nF")
      (footprint "eagle-import:C0603")
      (libsource (lib "eagle-import") (part "C-USC0603"))
    )
    (comp (ref "C214")
      (value "100nF")
      (footprint "eagle-import:C0603")
      (libsource (lib "eagle-import") (part "C-USC0603"))
    )
    (comp (ref "C215")
      (value "100nF")
      (footprint "eagle-import:C0603")
      (libsource (lib "eagle-import") (part "C-USC0603"))
    )
    (comp (ref "C216")
      (value "100nF")
      (footprint "eagle-import:C0603")
      (libsource (lib "eagle-import") (part "C-USC0603"))
    )
    (comp (ref "C217")
      (value "100nF")
      (footprint "eagle-import:C0603")
      (libsource (lib "eagle-import") (part "C-USC0603"))
    )
    (comp (ref "C218")
      (value "100nF")
      (footprint "eagle-import:C0603")
      (libsource (lib "eagle-import") (part "C-USC0603"))
    )
    (comp (ref "C219")
      (value "100nF")
      (footprint "eagle-import:C0603")
      (libsource (lib "eagle-import") (part "C-USC0603"))
    )
    (comp (ref "C220")
      (value "100nF")
      (footprint "eagle-import:C0603")
      (libsource (lib "eagle-import") (part "C-USC0603"))
    )
    (comp (ref "CB201")
      (value "100nF")
      (footprint "eagle-import:C0603")
      (libsource (lib "eagle-import") (part "C-USC0603"))
    )
    (comp (ref "CB202")
      (value "100nF")
      (footprint "eagle-import:C0603")
      (libsource (lib "eagle-import") (part "C-USC0603"))
    )
    (comp (ref "CB203")
      (value "100nF")
      (footprint "eagle-import:C0603")
      (libsource (lib "eagle-import") (part "C-USC0603"))
    )
    (comp (ref "CB204")
      (value "100nF")
      (footprint "eagle-import:C0603")
      (libsource (lib "eagle-import") (part "C-USC0603"))
    )
    (comp (ref "CB205")
      (value "100nF")
      (footprint "eagle-import:C0603")
      (libsource (lib "eagle-import") (part "C-USC0603"))
    )
    (comp (ref "CB206")
      (value "100nF")
      (footprint "eagle-import:C0603")
      (libsource (lib "eagle-import") (part "C-USC0603"))
    )
    (comp (ref "CB207")
      (value "100nF")
      (footprint "eagle-import:C0603")
      (libsource (lib "eagle-import") (part "C-USC0603"))
    )
    (comp (ref "CB208")
      (value "100nF")
      (footprint "eagle-import:C0603")
      (libsource (lib "eagle-import") (part "C-USC0603"))
    )
    (comp (ref "CB209")
      (value "100nF")
      (footprint "eagle-import:C0603")
      (libsource (lib "eagle-import") (part "C-USC0603"))
    )
    (comp (ref "CB210")
      (value "100nF")
      (footprint "eagle-import:C0603")
      (libsource (lib "eagle-import") (part "C-USC0603"))
    )
    (comp (ref "CB211")
      (value "100nF")
      (footprint "eagle-import:C0603")
      (libsource (lib "eagle-import") (part "C-USC0603"))
    )
    (comp (ref "CB212")
      (value "100nF")
      (footprint "eagle-import:C0603")
      (libsource (lib "eagle-import") (part "C-USC0603"))
    )
    (comp (ref "CB213")
      (value "1uF")
      (footprint "eagle-import:C0805")
      (libsource (lib "eagle-import") (part "C-USC0805"))
    )
    (comp (ref "CB214")
      (value "100nF")
      (footprint "eagle-import:C0603")
      (libsource (lib "eagle-import") (part "C-USC0603"))
    )
    (comp (ref "CB215")
      (value "1uF")
      (footprint "eagle-import:C0805")
      (libsource (lib "eagle-import") (part "C-USC0805"))
    )
    (comp (ref "CB216")
      (value "100nF")
      (footprint "eagle-import:C0603")
      (libsource (lib "eagle-import") (part "C-USC0603"))
    )
    (comp (ref "DDS")
      (value "AD9958")
      (footprint "eagle-import:LFCSP-56")
      (libsource (lib "eagle-import") (part "AD9958"))
    )
    (comp (ref "FB1")
      (value "R-US_R0603")
      (footprint "eagle-import:R0603")
      (libsource (lib "eagle-import") (part "R-US_R0603"))
    )
    (comp (ref "FB2")
      (value "R-US_R0603")
      (footprint "eagle-import:R0603")
      (libsource (lib "eagle-import") (part "R-US_R0603"))
    )
    (comp (ref "LF1")
      (value "330nH")
      (footprint "eagle-import:1008")
      (libsource (lib "eagle-import") (part "INDUCTOR1008"))
    )
    (comp (ref "LF2")
      (value "330nH")
      (footprint "eagle-import:1008")
      (libsource (lib "eagle-import") (part "INDUCTOR1008"))
    )
    (comp (ref "LO0")
      (value "BNC-EDGESMC")
      (footprint "eagle-import:SMC-EDGE")
      (libsource (lib "eagle-import") (part "BNC-EDGESMC"))
    )
    (comp (ref "LO1")
      (value "BNC-EDGESMC")
      (footprint "eagle-import:SMC-EDGE")
      (libsource (lib "eagle-import") (part "BNC-EDGESMC"))
    )
    (comp (ref "OP1")
      (value "AD8008")
      (footprint "eagle-import:SO08")
      (libsource (lib "eagle-import") (part "2AMP_P8+4D"))
    )
    (comp (ref "OP2")
      (value "AD8008")
      (footprint "eagle-import:SO08")
      (libsource (lib "eagle-import") (part "2AMP_P8+4D"))
    )
    (comp (ref "R201")
      (value "100")
      (footprint "eagle-import:R0805")
      (libsource (lib "eagle-import") (part "R-US_R0805"))
    )
    (comp (ref "R202")
      (value "220")
      (footprint "eagle-import:R0805")
      (libsource (lib "eagle-import") (part "R-US_R0805"))
    )
    (comp (ref "R203")
      (value "330")
      (footprint "eagle-import:R0805")
      (libsource (lib "eagle-import") (part "R-US_R0805"))
    )
    (comp (ref "R204")
      (value "220")
      (footprint "eagle-import:R0805")
      (libsource (lib "eagle-import") (part "R-US_R0805"))
    )
    (comp (ref "R205")
      (value "0")
      (footprint "eagle-import:R0805")
      (libsource (lib "eagle-import") (part "R-US_R0805"))
    )
    (comp (ref "R206")
      (value "2k")
      (footprint "eagle-import:R0805")
      (libsource (lib "eagle-import") (part "R-US_R0805"))
    )
    (comp (ref "R207")
      (value "49.9")
      (footprint "eagle-import:R0805")
      (libsource (lib "eagle-import") (part "R-US_R0805"))
    )
    (comp (ref "R208")
      (value "49.9")
      (footprint "eagle-import:R0805")
      (libsource (lib "eagle-import") (part "R-US_R0805"))
    )
    (comp (ref "R209")
      (value "49.9")
      (footprint "eagle-import:R0805")
      (libsource (lib "eagle-import") (part "R-US_R0805"))
    )
    (comp (ref "R210")
      (value "49.9")
      (footprint "eagle-import:R0805")
      (libsource (lib "eagle-import") (part "R-US_R0805"))
    )
    (comp (ref "R211")
      (value "13k")
      (footprint "eagle-import:R0805")
      (libsource (lib "eagle-import") (part "R-US_R0805"))
    )
    (comp (ref "R212")
      (value "13k")
      (footprint "eagle-import:R0805")
      (libsource (lib "eagle-import") (part "R-US_R0805"))
    )
    (comp (ref "R213")
      (value "200")
      (footprint "eagle-import:R0805")
      (libsource (lib "eagle-import") (part "R-US_R0805"))
    )
    (comp (ref "R214")
      (value "511")
      (footprint "eagle-import:R0805")
      (libsource (lib "eagle-import") (part "R-US_R0805"))
    )
    (comp (ref "R215")
      (value "100")
      (footprint "eagle-import:R0805")
      (libsource (lib "eagle-import") (part "R-US_R0805"))
    )
    (comp (ref "R216")
      (value "49.9")
      (footprint "eagle-import:R0805")
      (libsource (lib "eagle-import") (part "R-US_R0805"))
    )
    (comp (ref "R217")
      (value "200")
      (footprint "eagle-import:R0805")
      (libsource (lib "eagle-import") (part "R-US_R0805"))
    )
    (comp (ref "R218")
      (value "511")
      (footprint "eagle-import:R0805")
      (libsource (lib "eagle-import") (part "R-US_R0805"))
    )
    (comp (ref "R219")
      (value "100")
      (footprint "eagle-import:R0805")
      (libsource (lib "eagle-import") (part "R-US_R0805"))
    )
    (comp (ref "R220")
      (value "49.9")
      (footprint "eagle-import:R0805")
      (libsource (lib "eagle-import") (part "R-US_R0805"))
    )
    (comp (ref "R221")
      (value "49.9")
      (footprint "eagle-import:R0805")
      (libsource (lib "eagle-import") (part "R-US_R0805"))
    )
    (comp (ref "R222")
      (value "13k")
      (footprint "eagle-import:R0805")
      (libsource (lib "eagle-import") (part "R-US_R0805"))
    )
    (comp (ref "R223")
      (value "13k")
      (footprint "eagle-import:R0805")
      (libsource (lib "eagle-import") (part "R-US_R0805"))
    )
    (comp (ref "R224")
      (value "200")
      (footprint "eagle-import:R0805")
      (libsource (lib "eagle-import") (part "R-US_R0805"))
    )
    (comp (ref "R225")
      (value "511")
      (footprint "eagle-import:R0805")
      (libsource (lib "eagle-import") (part "R-US_R0805"))
    )
    (comp (ref "R226")
      (value "100")
      (footprint "eagle-import:R0805")
      (libsource (lib "eagle-import") (part "R-US_R0805"))
    )
    (comp (ref "R227")
      (value "49.9")
      (footprint "eagle-import:R0805")
      (libsource (lib "eagle-import") (part "R-US_R0805"))
    )
    (comp (ref "R228")
      (value "200")
      (footprint "eagle-import:R0805")
      (libsource (lib "eagle-import") (part "R-US_R0805"))
    )
    (comp (ref "R230")
      (value "100")
      (footprint "eagle-import:R0805")
      (libsource (lib "eagle-import") (part "R-US_R0805"))
    )
    (comp (ref "R231")
      (value "511")
      (footprint "eagle-import:R0805")
      (libsource (lib "eagle-import") (part "R-US_R0805"))
    )
    (comp (ref "R232")
      (value "49.9")
      (footprint "eagle-import:R0805")
      (libsource (lib "eagle-import") (part "R-US_R0805"))
    )
    (comp (ref "R233")
      (value "49.9")
      (footprint "eagle-import:R0805")
      (libsource (lib "eagle-import") (part "R-US_R0805"))
    )
    (comp (ref "SYNC")
      (value "TPTP10R")
      (footprint "eagle-import:TP10R")
      (libsource (lib "eagle-import") (part "TPTP10R"))
    )
    (comp (ref "T1")
      (value "CX2045")
      (footprint "eagle-import:CX20XX_BALUN")
      (libsource (lib "eagle-import") (part "BALUN_2{colon}1"))
    )
    (comp (ref "T2")
      (value "CX2045")
      (footprint "eagle-import:CX20XX_BALUN")
      (libsource (lib "eagle-import") (part "BALUN_2{colon}1"))
    )
    (comp (ref "T3")
      (value "RFXF9503")
      (footprint "eagle-import:CX20XX_BALUN")
      (libsource (lib "eagle-import") (part "amyparts-rf-combined_BALUN_2{colon}1"))
    )
    (comp (ref "TX0")
      (value "BNC-EDGESMC")
      (footprint "eagle-import:SMC-EDGE")
      (libsource (lib "eagle-import") (part "BNC-EDGESMC"))
    )
    (comp (ref "TX1")
      (value "BNC-EDGESMC")
      (footprint "eagle-import:SMC-EDGE")
      (libsource (lib "eagle-import") (part "BNC-EDGESMC"))
    )
    (comp (ref "+12VIN")
      (value "TERM-2OMNIMATE_SL")
      (footprint "eagle-import:OMNIMATE_SL_2POS")
      (libsource (lib "eagle-import") (part "TERM-2OMNIMATE_SL"))
    )
    (comp (ref "-12VOUT")
      (value "TERM-2OMNIMATE_SL")
      (footprint "eagle-import:OMNIMATE_SL_2POS")
      (libsource (lib "eagle-import") (part "TERM-2OMNIMATE_SL"))
    )
    (comp (ref "1.8REG")
      (value "LMZ1050X")
      (footprint "eagle-import:LLP-8")
      (libsource (lib "eagle-import") (part "LMZ1050X"))
    )
    (comp (ref "3.3REG1")
      (value "LMZ1050X")
      (footprint "eagle-import:LLP-8")
      (libsource (lib "eagle-import") (part "LMZ1050X"))
    )
    (comp (ref "3.3VREG2")
      (value "LT3060")
      (footprint "eagle-import:TSOT-8")
      (libsource (lib "eagle-import") (part "LT3060"))
    )
    (comp (ref "5VOUT")
      (value "TERM-2OMNIMATE_SL")
      (footprint "eagle-import:OMNIMATE_SL_2POS")
      (libsource (lib "eagle-import") (part "TERM-2OMNIMATE_SL"))
    )
    (comp (ref "5VREG")
      (value "LMZ22003")
      (footprint "eagle-import:TO-PMOD7")
      (libsource (lib "eagle-import") (part "LMZ22003"))
    )
    (comp (ref "C401")
      (value "0.47uF")
      (footprint "eagle-import:C0805")
      (libsource (lib "eagle-import") (part "C-USC0805"))
    )
    (comp (ref "C402")
      (value "10nF")
      (footprint "eagle-import:C0603")
      (libsource (lib "eagle-import") (part "C-USC0603"))
    )
    (comp (ref "C403")
      (value "10nF")
      (footprint "eagle-import:C0603")
      (libsource (lib "eagle-import") (part "C-USC0603"))
    )
    (comp (ref "C404")
      (value "470pF")
      (footprint "eagle-import:C0603")
      (libsource (lib "eagle-import") (part "C-USC0603"))
    )
    (comp (ref "C405")
      (value "470pF")
      (footprint "eagle-import:C0603")
      (libsource (lib "eagle-import") (part "C-USC0603"))
    )
    (comp (ref "C406")
      (value "NP")
      (footprint "eagle-import:C0805")
      (libsource (lib "eagle-import") (part "C-USC0805"))
    )
    (comp (ref "CB1")
      (value "10uF")
      (footprint "eagle-import:C0805")
      (libsource (lib "eagle-import") (part "C-USC0805"))
    )
    (comp (ref "CB401")
      (value "22uF")
      (footprint "eagle-import:C1210")
      (libsource (lib "eagle-import") (part "C-USC1210"))
    )
    (comp (ref "CB403")
      (value "220uF")
      (footprint "eagle-import:E3,5-8")
      (libsource (lib "eagle-import") (part "CPOL-USE3.5-8"))
    )
    (comp (ref "CB404")
      (value "10uF")
      (footprint "eagle-import:C0805")
      (libsource (lib "eagle-import") (part "C-USC0805"))
    )
    (comp (ref "CB405")
      (value "10uF")
      (footprint "eagle-import:C0805")
      (libsource (lib "eagle-import") (part "C-USC0805"))
    )
    (comp (ref "CB406")
      (value "10uF")
      (footprint "eagle-import:C0805")
      (libsource (lib "eagle-import") (part "C-USC0805"))
    )
    (comp (ref "CB407")
      (value "10uF")
      (footprint "eagle-import:C0805")
      (libsource (lib "eagle-import") (part "C-USC0805"))
    )
    (comp (ref "CB408")
      (value "1uF")
      (footprint "eagle-import:C0805")
      (libsource (lib "eagle-import") (part "C-USC0805"))
    )
    (comp (ref "CB409")
      (value "4.7uF")
      (footprint "eagle-import:C0805")
      (libsource (lib "eagle-import") (part "C-USC0805"))
    )
    (comp (ref "CB410")
      (value "10uF")
      (footprint "eagle-import:C0805")
      (libsource (lib "eagle-import") (part "C-USC0805"))
    )
    (comp (ref "CB411")
      (value "10uF")
      (footprint "eagle-import:C0805")
      (libsource (lib "eagle-import") (part "C-USC0805"))
    )
    (comp (ref "CB412")
      (value "22uF")
      (footprint "eagle-import:C1210")
      (libsource (lib "eagle-import") (part "C-USC1210"))
    )
    (comp (ref "CF")
      (value "10uF")
      (footprint "eagle-import:C0805")
      (libsource (lib "eagle-import") (part "C-USC0805"))
    )
    (comp (ref "D1")
      (value "NP")
      (footprint "eagle-import:SOD323-W")
      (libsource (lib "eagle-import") (part "DIODE-SOD323-W"))
    )
    (comp (ref "FB4")
      (value "R-US_R0805")
      (footprint "eagle-import:R0805")
      (libsource (lib "eagle-import") (part "R-US_R0805"))
    )
    (comp (ref "FB5")
      (value "R-US_R0603")
      (footprint "eagle-import:R0603")
      (libsource (lib "eagle-import") (part "R-US_R0603"))
    )
    (comp (ref "FB6")
      (value "R-US_R0603")
      (footprint "eagle-import:R0603")
      (libsource (lib "eagle-import") (part "R-US_R0603"))
    )
    (comp (ref "FB7")
      (value "R-US_R0603")
      (footprint "eagle-import:R0603")
      (libsource (lib "eagle-import") (part "R-US_R0603"))
    )
    (comp (ref "FB8")
      (value "R-US_R0603")
      (footprint "eagle-import:R0603")
      (libsource (lib "eagle-import") (part "R-US_R0603"))
    )
    (comp (ref "FUSE")
      (value "1206LXXXWR")
      (footprint "eagle-import:R1206")
      (libsource (lib "eagle-import") (part "R-US_R1206"))
    )
    (comp (ref "PUMP")
      (value "LT1054")
      (footprint "eagle-import:SOIC-8")
      (libsource (lib "eagle-import") (part "LT1054"))
    )
    (comp (ref "Q1")
      (value "BSS123")
      (footprint "eagle-import:SOT23")
      (libsource (lib "eagle-import") (part "BSS123"))
    )
    (comp (ref "Q2")
      (value "ZXMP6A13FTA")
      (footprint "eagle-import:SOT23")
      (libsource (lib "eagle-import") (part "BSS84"))
    )
    (comp (ref "Q3")
      (value "BSS123")
      (footprint "eagle-import:SOT23")
      (libsource (lib "eagle-import") (part "BSS123"))
    )
    (comp (ref "R401")
      (value "110k")
      (footprint "eagle-import:R0805")
      (libsource (lib "eagle-import") (part "R-US_R0805"))
    )
    (comp (ref "R402")
      (value "30.1k")
      (footprint "eagle-import:R0805")
      (libsource (lib "eagle-import") (part "R-US_R0805"))
    )
    (comp (ref "R403")
      (value "4.99k")
      (footprint "eagle-import:R0805")
      (libsource (lib "eagle-import") (part "R-US_R0805"))
    )
    (comp (ref "R404")
      (value "10K")
      (footprint "eagle-import:R0805")
      (libsource (lib "eagle-import") (part "R-US_R0805"))
    )
    (comp (ref "R405")
      (value "6.81K")
      (footprint "eagle-import:R0805")
      (libsource (lib "eagle-import") (part "R-US_R0805"))
    )
    (comp (ref "R406")
      (value "1.3K")
      (footprint "eagle-import:R0805")
      (libsource (lib "eagle-import") (part "R-US_R0805"))
    )
    (comp (ref "R407")
      (value "162k")
      (footprint "eagle-import:R0805")
      (libsource (lib "eagle-import") (part "R-US_R0805"))
    )
    (comp (ref "R408")
      (value "210k")
      (footprint "eagle-import:R0805")
      (libsource (lib "eagle-import") (part "R-US_R0805"))
    )
    (comp (ref "R409")
      (value "249k")
      (footprint "eagle-import:R0805")
      (libsource (lib "eagle-import") (part "R-US_R0805"))
    )
    (comp (ref "R410")
      (value "110k")
      (footprint "eagle-import:R0805")
      (libsource (lib "eagle-import") (part "R-US_R0805"))
    )
    (comp (ref "R411")
      (value "NP")
      (footprint "eagle-import:R0805")
      (libsource (lib "eagle-import") (part "R-US_R0805"))
    )
    (comp (ref "R412")
      (value "10K")
      (footprint "eagle-import:R0805")
      (libsource (lib "eagle-import") (part "R-US_R0805"))
    )
    (comp (ref "R413")
      (value "R-US_R0805")
      (footprint "eagle-import:R0805")
      (libsource (lib "eagle-import") (part "R-US_R0805"))
    )
    (comp (ref "R414")
      (value "R-US_R0805")
      (footprint "eagle-import:R0805")
      (libsource (lib "eagle-import") (part "R-US_R0805"))
    )
    (comp (ref "R415")
      (value "R-US_R0805")
      (footprint "eagle-import:R0805")
      (libsource (lib "eagle-import") (part "R-US_R0805"))
    )
    (comp (ref "R416")
      (value "21K")
      (footprint "eagle-import:R0805")
      (libsource (lib "eagle-import") (part "R-US_R0805"))
    )
    (comp (ref "R417")
      (value "249K")
      (footprint "eagle-import:R0805")
      (libsource (lib "eagle-import") (part "R-US_R0805"))
    )
    (comp (ref "Z1")
      (value "9.1V")
      (footprint "eagle-import:SOD123")
      (libsource (lib "eagle-import") (part "DIODE-SOD123"))
    )
    (comp (ref "Z2")
      (value "9.1V")
      (footprint "eagle-import:DO214AC")
      (libsource (lib "eagle-import") (part "DIODE-DO214AC"))
    )
    (comp (ref "Z3")
      (value "9.1V")
      (footprint "eagle-import:DO214AC")
      (libsource (lib "eagle-import") (part "DIODE-DO214AC"))
    )
  )
  (nets
    (net (code "1") (name "+5V") (class "Default")
      (node (ref "1.8REG") (pin "P$1") (pinfunction "EN_P$1") (pintype "input"))
      (node (ref "1.8REG") (pin "P$7") (pinfunction "VIN_P$7") (pintype "power_in"))
      (node (ref "3.3REG1") (pin "P$1") (pinfunction "EN_P$1") (pintype "input"))
      (node (ref "3.3REG1") (pin "P$7") (pinfunction "VIN_P$7") (pintype "power_in"))
      (node (ref "5VREG") (pin "P$7") (pinfunction "VOUT_P$7") (pintype "power_in"))
      (node (ref "CB116") (pin "1") (pinfunction "1_1") (pintype "passive"))
      (node (ref "CB117") (pin "1") (pinfunction "1_1") (pintype "passive"))
      (node (ref "CB403") (pin "+") (pinfunction "+_+") (pintype "passive"))
      (node (ref "CB404") (pin "1") (pinfunction "1_1") (pintype "passive"))
      (node (ref "CB406") (pin "1") (pinfunction "1_1") (pintype "passive"))
      (node (ref "FB1") (pin "1") (pinfunction "1_1") (pintype "passive"))
      (node (ref "FB2") (pin "1") (pinfunction "1_1") (pintype "passive"))
      (node (ref "FB7") (pin "1") (pinfunction "1_1") (pintype "passive"))
      (node (ref "FB8") (pin "2") (pinfunction "2_2") (pintype "passive"))
      (node (ref "FTDI") (pin "20") (pinfunction "VCC_20") (pintype "power_in"))
      (node (ref "R405") (pin "1") (pinfunction "1_1") (pintype "passive"))
    )
    (net (code "2") (name "+5V_SHDN") (class "Default")
      (node (ref "MCU") (pin "62") (pinfunction "PC14/PWM-PWML[2]/USART0-CLK/EBI-SDCKE/USART0-CTS_62") (pintype "bidirectional"))
      (node (ref "Q3") (pin "1") (pinfunction "G_1") (pintype "passive"))
      (node (ref "R404") (pin "1") (pinfunction "1_1") (pintype "passive"))
    )
    (net (code "3") (name "+12V") (class "Default")
      (node (ref "5VREG") (pin "P$1") (pinfunction "VIN_P$1") (pintype "power_in"))
      (node (ref "CB401") (pin "1") (pinfunction "1_1") (pintype "passive"))
      (node (ref "CB412") (pin "1") (pinfunction "1_1") (pintype "passive"))
      (node (ref "FB5") (pin "2") (pinfunction "2_2") (pintype "passive"))
      (node (ref "Q2") (pin "2") (pinfunction "S_2") (pintype "passive"))
      (node (ref "R402") (pin "1") (pinfunction "1_1") (pintype "passive"))
      (node (ref "Z1") (pin "C") (pinfunction "C_C") (pintype "passive"))
      (node (ref "Z2") (pin "C") (pinfunction "C_C") (pintype "passive"))
    )
    (net (code "4") (name "-12V_SHDN") (class "Default")
      (node (ref "MCU") (pin "61") (pinfunction "PC13/PWM-PWMH[2]/EIC-EXTINT[7]/EBI-SDCS/USART2-RTS_61") (pintype "bidirectional"))
      (node (ref "Q1") (pin "1") (pinfunction "G_1") (pintype "passive"))
      (node (ref "R412") (pin "1") (pinfunction "1_1") (pintype "passive"))
    )
    (net (code "5") (name "A1.8V") (class "Default")
      (node (ref "C204") (pin "2") (pinfunction "2_2") (pintype "passive"))
      (node (ref "CB201") (pin "1") (pinfunction "1_1") (pintype "passive"))
      (node (ref "CB202") (pin "1") (pinfunction "1_1") (pintype "passive"))
      (node (ref "CB203") (pin "1") (pinfunction "1_1") (pintype "passive"))
      (node (ref "CB204") (pin "1") (pinfunction "1_1") (pintype "passive"))
      (node (ref "CB205") (pin "1") (pinfunction "1_1") (pintype "passive"))
      (node (ref "CB206") (pin "1") (pinfunction "1_1") (pintype "passive"))
      (node (ref "CB207") (pin "1") (pinfunction "1_1") (pintype "passive"))
      (node (ref "CB208") (pin "1") (pinfunction "1_1") (pintype "passive"))
      (node (ref "CB212") (pin "1") (pinfunction "1_1") (pintype "passive"))
      (node (ref "DDS") (pin "11") (pinfunction "AVDD3_11") (pintype "power_in"))
      (node (ref "DDS") (pin "15") (pinfunction "AVDD4_15") (pintype "power_in"))
      (node (ref "DDS") (pin "19") (pinfunction "AVDD5_19") (pintype "power_in"))
      (node (ref "DDS") (pin "21") (pinfunction "AVDD6_21") (pintype "power_in"))
      (node (ref "DDS") (pin "26") (pinfunction "AVDD7_26") (pintype "power_in"))
      (node (ref "DDS") (pin "29") (pinfunction "AVDD8_29") (pintype "power_in"))
      (node (ref "DDS") (pin "30") (pinfunction "AVDD9_30") (pintype "power_in"))
      (node (ref "DDS") (pin "31") (pinfunction "AVDD10_31") (pintype "power_in"))
      (node (ref "DDS") (pin "33") (pinfunction "AVDD11_33") (pintype "power_in"))
      (node (ref "DDS") (pin "35") (pinfunction "AVDD12_35") (pintype "power_in"))
      (node (ref "DDS") (pin "36") (pinfunction "AVDD13_36") (pintype "power_in"))
      (node (ref "DDS") (pin "37") (pinfunction "AVDD14_37") (pintype "power_in"))
      (node (ref "DDS") (pin "39") (pinfunction "AVDD15_39") (pintype "power_in"))
      (node (ref "DDS") (pin "5") (pinfunction "AVDD1_5") (pintype "power_in"))
      (node (ref "DDS") (pin "7") (pinfunction "AVDD2_7") (pintype "power_in"))
      (node (ref "FB4") (pin "1") (pinfunction "1_1") (pintype "passive"))
      (node (ref "T1") (pin "P$2") (pinfunction "5_P$2") (pintype "passive"))
      (node (ref "T2") (pin "P$2") (pinfunction "5_P$2") (pintype "passive"))
    )
    (net (code "6") (name "A3.3V") (class "Default")
      (node (ref "3.3VREG2") (pin "6") (pinfunction "VOUT_6") (pintype "power_in"))
      (node (ref "ADC") (pin "7") (pinfunction "VDD_7") (pintype "power_in"))
      (node (ref "C403") (pin "1") (pinfunction "1_1") (pintype "passive"))
      (node (ref "CB301") (pin "1") (pinfunction "1_1") (pintype "passive"))
      (node (ref "CB305") (pin "1") (pinfunction "1_1") (pintype "passive"))
      (node (ref "CB306") (pin "1") (pinfunction "1_1") (pintype "passive"))
      (node (ref "CB307") (pin "1") (pinfunction "1_1") (pintype "passive"))
      (node (ref "CB308") (pin "1") (pinfunction "1_1") (pintype "passive"))
      (node (ref "CB409") (pin "1") (pinfunction "1_1") (pintype "passive"))
      (node (ref "OP3") (pin "4") (pinfunction "V+_4") (pintype "power_in"))
      (node (ref "OP4") (pin "5") (pinfunction "V+_5") (pintype "power_in"))
      (node (ref "REF1") (pin "3") (pinfunction "EN_3") (pintype "input"))
      (node (ref "REF1") (pin "4") (pinfunction "IN_4") (pintype "power_in"))
    )
    (net (code "7") (name "AVR1.8V") (class "Default")
      (node (ref "CB109") (pin "1") (pinfunction "1_1") (pintype "passive"))
      (node (ref "CB110") (pin "1") (pinfunction "1_1") (pintype "passive"))
      (node (ref "CB111") (pin "1") (pinfunction "1_1") (pintype "passive"))
      (node (ref "MCU") (pin "40") (pinfunction "VDDCORE_40") (pintype "power_in"))
    )
    (net (code "8") (name "CONV") (class "Default")
      (node (ref "ADC") (pin "10") (pinfunction "CONV_10") (pintype "input"))
      (node (ref "JP5") (pin "1") (pinfunction "1_1") (pintype "passive"))
      (node (ref "MCU") (pin "57") (pinfunction "PC06/PEVC-PAD_EVT[15]/USART2-CLK/USART2-CTS/TC0-CLK2/TWIMS2-TWD/TWIMS0-TWALM_57") (pintype "bidirectional"))
    )
    (net (code "9") (name "CS_DDS") (class "Default")
      (node (ref "CS_DDS") (pin "TP") (pinfunction "PP_TP") (pintype "input"))
      (node (ref "DDS") (pin "47") (pinfunction "~{CS}_47") (pintype "input"))
      (node (ref "MCU") (pin "45") (pinfunction "MACB-RXD[3]/TC0-A1/SPI1-NPCS[3]/IISC-ISCK/SCIF-GCLK[1]/PB22_45") (pintype "bidirectional"))
    )
    (net (code "10") (name "CS_SD") (class "Default")
      (node (ref "CS_SD") (pin "TP") (pinfunction "PP_TP") (pintype "input"))
      (node (ref "MCU") (pin "77") (pinfunction "PD03/SPI0-NPCS[0]/TC0-B0/EBI-ADDR[0]/QDEC0-QEPB_77") (pintype "bidirectional"))
      (node (ref "R106") (pin "2") (pinfunction "2_2") (pintype "passive"))
      (node (ref "SD") (pin "CD/DAT3") (pinfunction "DAT3/CS_CD/DAT3") (pintype "bidirectional"))
    )
    (net (code "11") (name "D1.8V") (class "Default")
      (node (ref "1.8REG") (pin "P$3") (pinfunction "FB_P$3") (pintype "passive"))
      (node (ref "1.8REG") (pin "P$5") (pinfunction "VOUT_P$5") (pintype "power_in"))
      (node (ref "CB209") (pin "1") (pinfunction "1_1") (pintype "passive"))
      (node (ref "CB210") (pin "1") (pinfunction "1_1") (pintype "passive"))
      (node (ref "CB407") (pin "1") (pinfunction "1_1") (pintype "passive"))
      (node (ref "DDS") (pin "45") (pinfunction "DVDD1_45") (pintype "power_in"))
      (node (ref "DDS") (pin "55") (pinfunction "DVDD2_55") (pintype "power_in"))
      (node (ref "FB4") (pin "2") (pinfunction "2_2") (pintype "passive"))
    )
    (net (code "12") (name "D3.3V") (class "Default")
      (node (ref "3.3REG1") (pin "P$3") (pinfunction "FB_P$3") (pintype "passive"))
      (node (ref "3.3REG1") (pin "P$5") (pinfunction "VOUT_P$5") (pintype "power_in"))
      (node (ref "CB101") (pin "1") (pinfunction "1_1") (pintype "passive"))
      (node (ref "CB102") (pin "1") (pinfunction "1_1") (pintype "passive"))
      (node (ref "CB103") (pin "1") (pinfunction "1_1") (pintype "passive"))
      (node (ref "CB104") (pin "1") (pinfunction "1_1") (pintype "passive"))
      (node (ref "CB105") (pin "1") (pinfunction "1_1") (pintype "passive"))
      (node (ref "CB106") (pin "1") (pinfunction "1_1") (pintype "passive"))
      (node (ref "CB112") (pin "1") (pinfunction "1_1") (pintype "passive"))
      (node (ref "CB113") (pin "1") (pinfunction "1_1") (pintype "passive"))
      (node (ref "CB114") (pin "1") (pinfunction "1_1") (pintype "passive"))
      (node (ref "CB115") (pin "1") (pinfunction "1_1") (pintype "passive"))
      (node (ref "CB121") (pin "1") (pinfunction "1_1") (pintype "passive"))
      (node (ref "CB122") (pin "1") (pinfunction "1_1") (pintype "passive"))
      (node (ref "CB126") (pin "1") (pinfunction "1_1") (pintype "passive"))
      (node (ref "CB211") (pin "1") (pinfunction "1_1") (pintype "passive"))
      (node (ref "CB405") (pin "1") (pinfunction "1_1") (pintype "passive"))
      (node (ref "CS1") (pin "1") (pinfunction "1_1") (pintype "passive"))
      (node (ref "DDS") (pin "49") (pinfunction "DVDD_IO_49") (pintype "power_in"))
      (node (ref "FB3") (pin "2") (pinfunction "2_2") (pintype "passive"))
      (node (ref "JTAG") (pin "4") (pinfunction "4_4") (pintype "passive"))
      (node (ref "LCD") (pin "1") (pinfunction "1_1") (pintype "passive"))
      (node (ref "MCU") (pin "38") (pinfunction "VDDIN_5_38") (pintype "power_in"))
      (node (ref "MCU") (pin "39") (pinfunction "VDDIN_33_39") (pintype "power_in"))
      (node (ref "MCU") (pin "5") (pinfunction "VDDIO_5") (pintype "power_in"))
      (node (ref "MCU") (pin "53") (pinfunction "VDDIO_53") (pintype "power_in"))
      (node (ref "MCU") (pin "82") (pinfunction "VDDIO_82") (pintype "power_in"))
      (node (ref "R101") (pin "2") (pinfunction "2_2") (pintype "passive"))
      (node (ref "R102") (pin "1") (pinfunction "1_1") (pintype "passive"))
      (node (ref "R106") (pin "1") (pinfunction "1_1") (pintype "passive"))
      (node (ref "R107") (pin "1") (pinfunction "1_1") (pintype "passive"))
      (node (ref "R108") (pin "1") (pinfunction "1_1") (pintype "passive"))
      (node (ref "R109") (pin "1") (pinfunction "1_1") (pintype "passive"))
      (node (ref "R110") (pin "1") (pinfunction "1_1") (pintype "passive"))
      (node (ref "R119") (pin "1") (pinfunction "1_1") (pintype "passive"))
      (node (ref "REFCLK") (pin "P$1") (pinfunction "OE_P$1") (pintype "input"))
      (node (ref "REFCLK") (pin "P$4") (pinfunction "VCC_P$4") (pintype "power_in"))
      (node (ref "SD") (pin "VDD") (pinfunction "VDD_VDD") (pintype "power_in"))
    )
    (net (code "13") (name "DAC0A") (class "Default")
      (node (ref "MCU") (pin "28") (pinfunction "ADCIN9/AC0AP0/DAC0A/PA20_28") (pintype "bidirectional"))
      (node (ref "R104") (pin "2") (pinfunction "2_2") (pintype "passive"))
    )
    (net (code "14") (name "DAC1A") (class "Default")
      (node (ref "MCU") (pin "18") (pinfunction "AC1AP0/SPIO-NPCS[0]/DAC1A/PA12_18") (pintype "bidirectional"))
      (node (ref "R105") (pin "2") (pinfunction "2_2") (pintype "passive"))
    )
    (net (code "15") (name "DACREF") (class "Default")
      (node (ref "CB125") (pin "1") (pinfunction "1_1") (pintype "passive"))
      (node (ref "DREF") (pin "1") (pinfunction "C_1") (pintype "passive"))
      (node (ref "MCU") (pin "22") (pinfunction "ADCREF0/DACREF/PA16_22") (pintype "bidirectional"))
      (node (ref "R118") (pin "2") (pinfunction "2_2") (pintype "passive"))
    )
    (net (code "16") (name "DDS_IOUPDATE") (class "Default")
      (node (ref "DDS") (pin "46") (pinfunction "I/O_UPDATE_46") (pintype "input"))
      (node (ref "MCU") (pin "46") (pinfunction "MACB-RX_CLK/TC0-B1/SPI1-NPCS[2]/IISC-IWS/PB23_46") (pintype "bidirectional"))
      (node (ref "UPDATE") (pin "TP") (pinfunction "PP_TP") (pintype "input"))
    )
    (net (code "17") (name "DDS_P0") (class "Default")
      (node (ref "DDS") (pin "40") (pinfunction "P0_40") (pintype "input"))
      (node (ref "MCU") (pin "52") (pinfunction "PC03/TWIMSO-TWCK/EIC-EXTINT[1]/USART2-TXD/TC1-B1/MACB-MDIO_52") (pintype "bidirectional"))
      (node (ref "P0") (pin "TP") (pinfunction "PP_TP") (pintype "input"))
    )
    (net (code "18") (name "DDS_P1") (class "Default")
      (node (ref "DDS") (pin "41") (pinfunction "P1_41") (pintype "input"))
      (node (ref "MCU") (pin "51") (pinfunction "PC02/TWIMS0-TWD/SPI0-NPCS[3]/USART2-RXD/TC1-CLK1/MACB-MDC_51") (pintype "bidirectional"))
      (node (ref "P1") (pin "TP") (pinfunction "PP_TP") (pintype "input"))
    )
    (net (code "19") (name "DDS_P2") (class "Default")
      (node (ref "DDS") (pin "42") (pinfunction "P2_42") (pintype "input"))
      (node (ref "MCU") (pin "50") (pinfunction "PC01/USB-VBOF/SPI0-NPCS[2]/USART2-RTS/TC1-A2/CANIF-RXLINE[1]_50") (pintype "bidirectional"))
      (node (ref "P2") (pin "TP") (pinfunction "PP_TP") (pintype "input"))
    )
    (net (code "20") (name "DDS_P3") (class "Default")
      (node (ref "DDS") (pin "43") (pinfunction "P3_43") (pintype "input"))
      (node (ref "MCU") (pin "49") (pinfunction "PC00/USB-ID/SPI0-NPCS[1]/USART2-CTS/TC1-B2/CANIF-TXLINE[1]_49") (pintype "bidirectional"))
      (node (ref "P3") (pin "TP") (pinfunction "PP_TP") (pintype "input"))
    )
    (net (code "21") (name "DDS_PDN") (class "Default")
      (node (ref "DDS") (pin "4") (pinfunction "PWR_DWN_4") (pintype "input"))
      (node (ref "DDSPDN") (pin "TP") (pinfunction "PP_TP") (pintype "input"))
      (node (ref "MCU") (pin "17") (pinfunction "ADCIN7/ADCREF1/PEVC-PAD_EVT[14]/PA11_17") (pintype "bidirectional"))
    )
    (net (code "22") (name "DDS_RESET") (class "Default")
      (node (ref "DDS") (pin "3") (pinfunction "MASTER_RESET_3") (pintype "input"))
      (node (ref "DDSRESET") (pin "TP") (pinfunction "PP_TP") (pintype "input"))
      (node (ref "MCU") (pin "19") (pinfunction "ADCIN15/AC1AN0/SPI0-NPCS[1]/PA13_19") (pintype "bidirectional"))
    )
    (net (code "23") (name "DGND") (class "Default")
      (node (ref "USB") (pin "5") (pinfunction "5_5") (pintype "input"))
    )
    (net (code "24") (name "GEN1") (class "Default")
      (node (ref "JP3") (pin "4") (pinfunction "4_4") (pintype "passive"))
      (node (ref "MCU") (pin "15") (pinfunction "ADCIN5/AC1BN1/PA09_15") (pintype "bidirectional"))
    )
    (net (code "25") (name "GEN2") (class "Default")
      (node (ref "JP3") (pin "2") (pinfunction "2_2") (pintype "passive"))
      (node (ref "MCU") (pin "16") (pinfunction "ADCIN6/EIC-EXTINT[4]/PEVC-PAD_EVT[13]/PA10_16") (pintype "bidirectional"))
    )
    (net (code "26") (name "GND") (class "Default")
      (node (ref "+12VIN") (pin "2") (pinfunction "2_2") (pintype "passive"))
      (node (ref "-12VOUT") (pin "2") (pinfunction "2_2") (pintype "passive"))
      (node (ref "1.8REG") (pin "EP") (pinfunction "EP_EP") (pintype "power_in"))
      (node (ref "1.8REG") (pin "P$4") (pinfunction "SGND_P$4") (pintype "power_in"))
      (node (ref "1.8REG") (pin "P$6") (pinfunction "PGND_P$6") (pintype "power_in"))
      (node (ref "3.3REG1") (pin "EP") (pinfunction "EP_EP") (pintype "power_in"))
      (node (ref "3.3REG1") (pin "P$4") (pinfunction "SGND_P$4") (pintype "power_in"))
      (node (ref "3.3REG1") (pin "P$6") (pinfunction "PGND_P$6") (pintype "power_in"))
      (node (ref "3.3VREG2") (pin "2") (pinfunction "GND1_2") (pintype "power_in"))
      (node (ref "3.3VREG2") (pin "3") (pinfunction "GND2_3") (pintype "power_in"))
      (node (ref "3.3VREG2") (pin "4") (pinfunction "GND3_4") (pintype "power_in"))
      (node (ref "5VREG") (pin "EP") (pinfunction "EP_EP") (pintype "power_in"))
      (node (ref "5VREG") (pin "P$2") (pinfunction "SYNC_P$2") (pintype "input"))
      (node (ref "5VREG") (pin "P$4") (pinfunction "AGND_P$4") (pintype "power_in"))
      (node (ref "ADC") (pin "6") (pinfunction "GND_6") (pintype "power_in"))
      (node (ref "ADC") (pin "EXP") (pinfunction "EXP_EXP") (pintype "power_in"))
      (node (ref "C205") (pin "P$2") (pinfunction "2_P$2") (pintype "passive"))
      (node (ref "C206") (pin "P$2") (pinfunction "2_P$2") (pintype "passive"))
      (node (ref "C207") (pin "P$2") (pinfunction "2_P$2") (pintype "passive"))
      (node (ref "C208") (pin "P$2") (pinfunction "2_P$2") (pintype "passive"))
      (node (ref "C209") (pin "2") (pinfunction "2_2") (pintype "passive"))
      (node (ref "C210") (pin "2") (pinfunction "2_2") (pintype "passive"))
      (node (ref "C214") (pin "2") (pinfunction "2_2") (pintype "passive"))
      (node (ref "C215") (pin "2") (pinfunction "2_2") (pintype "passive"))
      (node (ref "C401") (pin "2") (pinfunction "2_2") (pintype "passive"))
      (node (ref "C402") (pin "2") (pinfunction "2_2") (pintype "passive"))
      (node (ref "C404") (pin "2") (pinfunction "2_2") (pintype "passive"))
      (node (ref "C405") (pin "2") (pinfunction "2_2") (pintype "passive"))
      (node (ref "CB1") (pin "2") (pinfunction "2_2") (pintype "passive"))
      (node (ref "CB101") (pin "2") (pinfunction "2_2") (pintype "passive"))
      (node (ref "CB102") (pin "2") (pinfunction "2_2") (pintype "passive"))
      (node (ref "CB103") (pin "2") (pinfunction "2_2") (pintype "passive"))
      (node (ref "CB104") (pin "2") (pinfunction "2_2") (pintype "passive"))
      (node (ref "CB105") (pin "2") (pinfunction "2_2") (pintype "passive"))
      (node (ref "CB106") (pin "2") (pinfunction "2_2") (pintype "passive"))
      (node (ref "CB107") (pin "2") (pinfunction "2_2") (pintype "passive"))
      (node (ref "CB108") (pin "2") (pinfunction "2_2") (pintype "passive"))
      (node (ref "CB109") (pin "2") (pinfunction "2_2") (pintype "passive"))
      (node (ref "CB110") (pin "2") (pinfunction "2_2") (pintype "passive"))
      (node (ref "CB111") (pin "2") (pinfunction "2_2") (pintype "passive"))
      (node (ref "CB112") (pin "2") (pinfunction "2_2") (pintype "passive"))
      (node (ref "CB113") (pin "2") (pinfunction "2_2") (pintype "passive"))
      (node (ref "CB114") (pin "2") (pinfunction "2_2") (pintype "passive"))
      (node (ref "CB115") (pin "2") (pinfunction "2_2") (pintype "passive"))
      (node (ref "CB116") (pin "2") (pinfunction "2_2") (pintype "passive"))
      (node (ref "CB117") (pin "2") (pinfunction "2_2") (pintype "passive"))
      (node (ref "CB118") (pin "2") (pinfunction "2_2") (pintype "passive"))
      (node (ref "CB119") (pin "2") (pinfunction "2_2") (pintype "passive"))
      (node (ref "CB120") (pin "2") (pinfunction "2_2") (pintype "passive"))
      (node (ref "CB121") (pin "2") (pinfunction "2_2") (pintype "passive"))
      (node (ref "CB122") (pin "2") (pinfunction "2_2") (pintype "passive"))
      (node (ref "CB123") (pin "2") (pinfunction "2_2") (pintype "passive"))
      (node (ref "CB125") (pin "2") (pinfunction "2_2") (pintype "passive"))
      (node (ref "CB126") (pin "2") (pinfunction "2_2") (pintype "passive"))
      (node (ref "CB201") (pin "2") (pinfunction "2_2") (pintype "passive"))
      (node (ref "CB202") (pin "2") (pinfunction "2_2") (pintype "passive"))
      (node (ref "CB203") (pin "2") (pinfunction "2_2") (pintype "passive"))
      (node (ref "CB204") (pin "2") (pinfunction "2_2") (pintype "passive"))
      (node (ref "CB205") (pin "2") (pinfunction "2_2") (pintype "passive"))
      (node (ref "CB206") (pin "2") (pinfunction "2_2") (pintype "passive"))
      (node (ref "CB207") (pin "2") (pinfunction "2_2") (pintype "passive"))
      (node (ref "CB208") (pin "2") (pinfunction "2_2") (pintype "passive"))
      (node (ref "CB209") (pin "2") (pinfunction "2_2") (pintype "passive"))
      (node (ref "CB210") (pin "2") (pinfunction "2_2") (pintype "passive"))
      (node (ref "CB211") (pin "2") (pinfunction "2_2") (pintype "passive"))
      (node (ref "CB212") (pin "2") (pinfunction "2_2") (pintype "passive"))
      (node (ref "CB213") (pin "2") (pinfunction "2_2") (pintype "passive"))
      (node (ref "CB214") (pin "2") (pinfunction "2_2") (pintype "passive"))
      (node (ref "CB215") (pin "2") (pinfunction "2_2") (pintype "passive"))
      (node (ref "CB216") (pin "2") (pinfunction "2_2") (pintype "passive"))
      (node (ref "CB301") (pin "2") (pinfunction "2_2") (pintype "passive"))
      (node (ref "CB302") (pin "2") (pinfunction "2_2") (pintype "passive"))
      (node (ref "CB303") (pin "2") (pinfunction "2_2") (pintype "passive"))
      (node (ref "CB304") (pin "2") (pinfunction "2_2") (pintype "passive"))
      (node (ref "CB305") (pin "2") (pinfunction "2_2") (pintype "passive"))
      (node (ref "CB306") (pin "2") (pinfunction "2_2") (pintype "passive"))
      (node (ref "CB307") (pin "2") (pinfunction "2_2") (pintype "passive"))
      (node (ref "CB308") (pin "2") (pinfunction "2_2") (pintype "passive"))
      (node (ref "CB309") (pin "2") (pinfunction "2_2") (pintype "passive"))
      (node (ref "CB310") (pin "2") (pinfunction "2_2") (pintype "passive"))
      (node (ref "CB401") (pin "2") (pinfunction "2_2") (pintype "passive"))
      (node (ref "CB403") (pin "-") (pinfunction "-_-") (pintype "passive"))
      (node (ref "CB404") (pin "2") (pinfunction "2_2") (pintype "passive"))
      (node (ref "CB405") (pin "2") (pinfunction "2_2") (pintype "passive"))
      (node (ref "CB406") (pin "2") (pinfunction "2_2") (pintype "passive"))
      (node (ref "CB407") (pin "2") (pinfunction "2_2") (pintype "passive"))
      (node (ref "CB408") (pin "2") (pinfunction "2_2") (pintype "passive"))
      (node (ref "CB409") (pin "2") (pinfunction "2_2") (pintype "passive"))
      (node (ref "CB410") (pin "2") (pinfunction "2_2") (pintype "passive"))
      (node (ref "CB411") (pin "2") (pinfunction "2_2") (pintype "passive"))
      (node (ref "CB412") (pin "2") (pinfunction "2_2") (pintype "passive"))
      (node (ref "CF301") (pin "2") (pinfunction "2_2") (pintype "passive"))
      (node (ref "CF303") (pin "2") (pinfunction "2_2") (pintype "passive"))
      (node (ref "CF305") (pin "2") (pinfunction "2_2") (pintype "passive"))
      (node (ref "CF306") (pin "2") (pinfunction "2_2") (pintype "passive"))
      (node (ref "CF308") (pin "2") (pinfunction "2_2") (pintype "passive"))
      (node (ref "CF310") (pin "2") (pinfunction "2_2") (pintype "passive"))
      (node (ref "CF311") (pin "2") (pinfunction "2_2") (pintype "passive"))
      (node (ref "CH0/I") (pin "2") (pinfunction "GND1_2") (pintype "power_in"))
      (node (ref "CH0/I") (pin "3") (pinfunction "GND2_3") (pintype "power_in"))
      (node (ref "CH1/Q") (pin "2") (pinfunction "GND1_2") (pintype "power_in"))
      (node (ref "CH1/Q") (pin "3") (pinfunction "GND2_3") (pintype "power_in"))
      (node (ref "CS1") (pin "2") (pinfunction "2_2") (pintype "passive"))
      (node (ref "D1") (pin "A") (pinfunction "A_A") (pintype "passive"))
      (node (ref "DDS") (pin "10") (pinfunction "AGND2_10") (pintype "power_in"))
      (node (ref "DDS") (pin "12") (pinfunction "AGND3_12") (pintype "power_in"))
      (node (ref "DDS") (pin "16") (pinfunction "AGND4_16") (pintype "power_in"))
      (node (ref "DDS") (pin "18") (pinfunction "AGND5_18") (pintype "power_in"))
      (node (ref "DDS") (pin "20") (pinfunction "AGND6_20") (pintype "power_in"))
      (node (ref "DDS") (pin "24") (pinfunction "CLK_MODE_SEL_24") (pintype "input"))
      (node (ref "DDS") (pin "25") (pinfunction "AGND7_25") (pintype "power_in"))
      (node (ref "DDS") (pin "44") (pinfunction "DGND1_44") (pintype "power_in"))
      (node (ref "DDS") (pin "53") (pinfunction "SDIO3_53") (pintype "bidirectional"))
      (node (ref "DDS") (pin "56") (pinfunction "DGND2_56") (pintype "power_in"))
      (node (ref "DDS") (pin "6") (pinfunction "AGND1_6") (pintype "power_in"))
      (node (ref "DDS") (pin "EXP") (pinfunction "PAD_EXP") (pintype "power_in"))
      (node (ref "DREF") (pin "2") (pinfunction "A_2") (pintype "passive"))
      (node (ref "FB6") (pin "1") (pinfunction "1_1") (pintype "passive"))
      (node (ref "FTDI") (pin "18") (pinfunction "GND2_18") (pintype "power_in"))
      (node (ref "FTDI") (pin "21") (pinfunction "GND3_21") (pintype "power_in"))
      (node (ref "FTDI") (pin "25") (pinfunction "AGND_25") (pintype "power_in"))
      (node (ref "FTDI") (pin "26") (pinfunction "TEST_26") (pintype "input"))
      (node (ref "FTDI") (pin "7") (pinfunction "GND1_7") (pintype "power_in"))
      (node (ref "JP1") (pin "2") (pinfunction "2_2") (pintype "passive"))
      (node (ref "JP1") (pin "4") (pinfunction "4_4") (pintype "passive"))
      (node (ref "JP3") (pin "1") (pinfunction "1_1") (pintype "passive"))
      (node (ref "JP3") (pin "11") (pinfunction "11_11") (pintype "passive"))
      (node (ref "JP3") (pin "13") (pinfunction "13_13") (pintype "passive"))
      (node (ref "JP3") (pin "3") (pinfunction "3_3") (pintype "passive"))
      (node (ref "JP3") (pin "5") (pinfunction "5_5") (pintype "passive"))
      (node (ref "JP3") (pin "7") (pinfunction "7_7") (pintype "passive"))
      (node (ref "JP3") (pin "9") (pinfunction "9_9") (pintype "passive"))
      (node (ref "JTAG") (pin "10") (pinfunction "10_10") (pintype "passive"))
      (node (ref "JTAG") (pin "2") (pinfunction "2_2") (pintype "passive"))
      (node (ref "LCD") (pin "3") (pinfunction "3_3") (pintype "passive"))
      (node (ref "LO0") (pin "2") (pinfunction "GND1_2") (pintype "power_in"))
      (node (ref "LO0") (pin "3") (pinfunction "GND2_3") (pintype "power_in"))
      (node (ref "LO1") (pin "2") (pinfunction "GND1_2") (pintype "power_in"))
      (node (ref "LO1") (pin "3") (pinfunction "GND2_3") (pintype "power_in"))
      (node (ref "MCU") (pin "26") (pinfunction "GNDANA_26") (pintype "power_in"))
      (node (ref "MCU") (pin "37") (pinfunction "GNDPLL_37") (pintype "power_in"))
      (node (ref "MCU") (pin "41") (pinfunction "GNDCORE_41") (pintype "power_in"))
      (node (ref "MCU") (pin "54") (pinfunction "GNDIO_54") (pintype "power_in"))
      (node (ref "MCU") (pin "6") (pinfunction "GNDIO_6") (pintype "power_in"))
      (node (ref "MCU") (pin "83") (pinfunction "GNDIO_83") (pintype "power_in"))
      (node (ref "MX0") (pin "P$1") (pinfunction "LON_P$1") (pintype "passive"))
      (node (ref "MX0") (pin "P$5") (pinfunction "GND_P$5") (pintype "passive"))
      (node (ref "MX1") (pin "P$1") (pinfunction "LON_P$1") (pintype "passive"))
      (node (ref "MX1") (pin "P$5") (pinfunction "GND_P$5") (pintype "passive"))
      (node (ref "OP1") (pin "4") (pinfunction "V-_4") (pintype "power_in"))
      (node (ref "OP2") (pin "4") (pinfunction "V-_4") (pintype "power_in"))
      (node (ref "OP3") (pin "11") (pinfunction "V-_11") (pintype "power_in"))
      (node (ref "OP4") (pin "2") (pinfunction "V-_2") (pintype "power_in"))
      (node (ref "PUMP") (pin "3") (pinfunction "GND_3") (pintype "power_in"))
      (node (ref "Q1") (pin "2") (pinfunction "S_2") (pintype "passive"))
      (node (ref "Q3") (pin "2") (pinfunction "S_2") (pintype "passive"))
      (node (ref "R113") (pin "2") (pinfunction "2_2") (pintype "passive"))
      (node (ref "R117") (pin "2") (pinfunction "2_2") (pintype "passive"))
      (node (ref "R120") (pin "1") (pinfunction "1_1") (pintype "passive"))
      (node (ref "R202") (pin "1") (pinfunction "1_1") (pintype "passive"))
      (node (ref "R204") (pin "2") (pinfunction "2_2") (pintype "passive"))
      (node (ref "R206") (pin "1") (pinfunction "1_1") (pintype "passive"))
      (node (ref "R207") (pin "1") (pinfunction "1_1") (pintype "passive"))
      (node (ref "R208") (pin "1") (pinfunction "1_1") (pintype "passive"))
      (node (ref "R209") (pin "1") (pinfunction "1_1") (pintype "passive"))
      (node (ref "R210") (pin "1") (pinfunction "1_1") (pintype "passive"))
      (node (ref "R211") (pin "1") (pinfunction "1_1") (pintype "passive"))
      (node (ref "R222") (pin "1") (pinfunction "1_1") (pintype "passive"))
      (node (ref "R301") (pin "1") (pinfunction "1_1") (pintype "passive"))
      (node (ref "R302") (pin "1") (pinfunction "1_1") (pintype "passive"))
      (node (ref "R311") (pin "1") (pinfunction "1_1") (pintype "passive"))
      (node (ref "R312") (pin "1") (pinfunction "1_1") (pintype "passive"))
      (node (ref "R323") (pin "2") (pinfunction "2_2") (pintype "passive"))
      (node (ref "R325") (pin "2") (pinfunction "2_2") (pintype "passive"))
      (node (ref "R401") (pin "1") (pinfunction "1_1") (pintype "passive"))
      (node (ref "R403") (pin "2") (pinfunction "2_2") (pintype "passive"))
      (node (ref "R404") (pin "2") (pinfunction "2_2") (pintype "passive"))
      (node (ref "R406") (pin "2") (pinfunction "2_2") (pintype "passive"))
      (node (ref "R408") (pin "2") (pinfunction "2_2") (pintype "passive"))
      (node (ref "R410") (pin "1") (pinfunction "1_1") (pintype "passive"))
      (node (ref "R412") (pin "2") (pinfunction "2_2") (pintype "passive"))
      (node (ref "R413") (pin "2") (pinfunction "2_2") (pintype "passive"))
      (node (ref "R414") (pin "2") (pinfunction "2_2") (pintype "passive"))
      (node (ref "R415") (pin "2") (pinfunction "2_2") (pintype "passive"))
      (node (ref "REF1") (pin "1") (pinfunction "GND_F_1") (pintype "power_in"))
      (node (ref "REF1") (pin "2") (pinfunction "GND_S_2") (pintype "passive"))
      (node (ref "REFCLK") (pin "P$2") (pinfunction "GND_P$2") (pintype "power_in"))
      (node (ref "RESET") (pin "P$1") (pinfunction "0_P$1") (pintype "passive"))
      (node (ref "RESET") (pin "P$3") (pinfunction "0_P$3") (pintype "passive"))
      (node (ref "SD") (pin "M1") (pinfunction "M1_M1") (pintype "passive"))
      (node (ref "SD") (pin "M2") (pinfunction "M2_M2") (pintype "passive"))
      (node (ref "SD") (pin "M3") (pinfunction "M3_M3") (pintype "passive"))
      (node (ref "SD") (pin "M4") (pinfunction "M4_M4") (pintype "passive"))
      (node (ref "SD") (pin "SWA") (pinfunction "SWA_SWA") (pintype "passive"))
      (node (ref "SD") (pin "VSS") (pinfunction "VSS_VSS") (pintype "power_in"))
      (node (ref "T1") (pin "P$4") (pinfunction "3_P$4") (pintype "passive"))
      (node (ref "T2") (pin "P$4") (pinfunction "3_P$4") (pintype "passive"))
      (node (ref "T3") (pin "P$3") (pinfunction "4_P$3") (pintype "passive"))
      (node (ref "TX0") (pin "2") (pinfunction "GND1_2") (pintype "power_in"))
      (node (ref "TX0") (pin "3") (pinfunction "GND2_3") (pintype "power_in"))
      (node (ref "TX1") (pin "2") (pinfunction "GND1_2") (pintype "power_in"))
      (node (ref "TX1") (pin "3") (pinfunction "GND2_3") (pintype "power_in"))
      (node (ref "U$1") (pin "P$1") (pinfunction "TP_P$1") (pintype "input"))
      (node (ref "U$2") (pin "P$1") (pinfunction "TP_P$1") (pintype "input"))
      (node (ref "U$3") (pin "P$1") (pinfunction "TP_P$1") (pintype "input"))
      (node (ref "U$4") (pin "P$1") (pinfunction "TP_P$1") (pintype "input"))
      (node (ref "U$5") (pin "P$1") (pinfunction "TP_P$1") (pintype "input"))
      (node (ref "Z3") (pin "A") (pinfunction "A_A") (pintype "passive"))
    )
    (net (code "27") (name "LO0") (class "Default")
      (node (ref "C212") (pin "1") (pinfunction "1_1") (pintype "passive"))
      (node (ref "MX0") (pin "P$6") (pinfunction "LOP_P$6") (pintype "passive"))
    )
    (net (code "28") (name "LO1") (class "Default")
      (node (ref "C217") (pin "1") (pinfunction "1_1") (pintype "passive"))
      (node (ref "MX1") (pin "P$6") (pinfunction "LOP_P$6") (pintype "passive"))
    )
    (net (code "29") (name "MCLK") (class "Default")
      (node (ref "CLK") (pin "TP") (pinfunction "PP_TP") (pintype "input"))
      (node (ref "MCU") (pin "47") (pinfunction "XIN0/PB30_47") (pintype "bidirectional"))
      (node (ref "R201") (pin "2") (pinfunction "2_2") (pintype "passive"))
      (node (ref "REFCLK") (pin "P$3") (pinfunction "FO_P$3") (pintype "output"))
    )
    (net (code "30") (name "MISO_0") (class "Default")
      (node (ref "MCU") (pin "75") (pinfunction "PD01/SPI0-MISO/TC1-A0/EBI-DATA[14]/TC0-CLK1/USART0-RXD_75") (pintype "bidirectional"))
      (node (ref "MISO0") (pin "TP") (pinfunction "PP_TP") (pintype "input"))
      (node (ref "R109") (pin "2") (pinfunction "2_2") (pintype "passive"))
      (node (ref "SD") (pin "DAT0") (pinfunction "DAT0/DO_DAT0") (pintype "bidirectional"))
    )
    (net (code "31") (name "MISO_1") (class "Default")
      (node (ref "ADC") (pin "8") (pinfunction "SDO_8") (pintype "output"))
      (node (ref "DDS") (pin "52") (pinfunction "SDIO2_52") (pintype "bidirectional"))
      (node (ref "JP5") (pin "3") (pinfunction "3_3") (pintype "passive"))
      (node (ref "MCU") (pin "43") (pinfunction "MACB-COL/TC0-B0/SPI1-MISO/IISC-ISDI/AC1FA1-ACAOUT/PB20_43") (pintype "bidirectional"))
    )
    (net (code "32") (name "MOSI_0") (class "Default")
      (node (ref "MCU") (pin "74") (pinfunction "PD00/SPI0-MOSI/TC1-CLK0/EBI-DATA[13]/QDEC0-QEPI/USART0-TXD_74") (pintype "bidirectional"))
      (node (ref "MOSI0") (pin "TP") (pinfunction "PP_TP") (pintype "input"))
      (node (ref "R110") (pin "2") (pinfunction "2_2") (pintype "passive"))
      (node (ref "SD") (pin "CMD") (pinfunction "CMD/DI_CMD") (pintype "input"))
    )
    (net (code "33") (name "MOSI_1") (class "Default")
      (node (ref "DDS") (pin "50") (pinfunction "SDIO0_50") (pintype "bidirectional"))
      (node (ref "JP5") (pin "4") (pinfunction "4_4") (pintype "passive"))
      (node (ref "MCU") (pin "42") (pinfunction "MACB-CRS/TC0-A0/SPI1-MOSI/IISC-ISDO/PB19_42") (pintype "bidirectional"))
    )
    (net (code "34") (name "MOUNT1") (class "Default")
      (node (ref "R415") (pin "1") (pinfunction "1_1") (pintype "passive"))
    )
    (net (code "35") (name "MOUNT2") (class "Default")
      (node (ref "R414") (pin "1") (pinfunction "1_1") (pintype "passive"))
    )
    (net (code "36") (name "MOUNT3") (class "Default")
      (node (ref "R413") (pin "1") (pinfunction "1_1") (pintype "passive"))
    )
    (net (code "37") (name "Net-(+12VIN-Pad1)") (class "Default")
      (node (ref "+12VIN") (pin "1") (pinfunction "1_1") (pintype "passive"))
      (node (ref "FUSE") (pin "2") (pinfunction "2_2") (pintype "passive"))
    )
    (net (code "38") (name "Net-(1.8REG-VCON)") (class "Default")
      (node (ref "1.8REG") (pin "P$2") (pinfunction "VCON_P$2") (pintype "passive"))
      (node (ref "C405") (pin "1") (pinfunction "1_1") (pintype "passive"))
      (node (ref "R409") (pin "1") (pinfunction "1_1") (pintype "passive"))
      (node (ref "R410") (pin "2") (pinfunction "2_2") (pintype "passive"))
    )
    (net (code "39") (name "Net-(1.8REG-VREF)") (class "Default")
      (node (ref "1.8REG") (pin "P$8") (pinfunction "VREF_P$8") (pintype "passive"))
      (node (ref "R409") (pin "2") (pinfunction "2_2") (pintype "passive"))
    )
    (net (code "40") (name "Net-(3.3REG1-VCON)") (class "Default")
      (node (ref "3.3REG1") (pin "P$2") (pinfunction "VCON_P$2") (pintype "passive"))
      (node (ref "C404") (pin "1") (pinfunction "1_1") (pintype "passive"))
      (node (ref "R407") (pin "2") (pinfunction "2_2") (pintype "passive"))
      (node (ref "R408") (pin "1") (pinfunction "1_1") (pintype "passive"))
    )
    (net (code "41") (name "Net-(3.3REG1-VREF)") (class "Default")
      (node (ref "3.3REG1") (pin "P$8") (pinfunction "VREF_P$8") (pintype "passive"))
      (node (ref "R407") (pin "1") (pinfunction "1_1") (pintype "passive"))
    )
    (net (code "42") (name "Net-(3.3VREG2-ADJ)") (class "Default")
      (node (ref "3.3VREG2") (pin "7") (pinfunction "ADJ_7") (pintype "passive"))
      (node (ref "C403") (pin "2") (pinfunction "2_2") (pintype "passive"))
    )
    (net (code "43") (name "Net-(3.3VREG2-REF{slash}BYP)") (class "Default")
      (node (ref "3.3VREG2") (pin "8") (pinfunction "REF/BYP_8") (pintype "passive"))
      (node (ref "C402") (pin "1") (pinfunction "1_1") (pintype "passive"))
    )
    (net (code "44") (name "Net-(3.3VREG2-VIN)") (class "Default")
      (node (ref "3.3VREG2") (pin "1") (pinfunction "~{SHDN}_1") (pintype "input"))
      (node (ref "3.3VREG2") (pin "5") (pinfunction "VIN_5") (pintype "power_in"))
      (node (ref "CB408") (pin "1") (pinfunction "1_1") (pintype "passive"))
      (node (ref "FB8") (pin "1") (pinfunction "1_1") (pintype "passive"))
    )
    (net (code "45") (name "Net-(5VOUT-Pad1)") (class "Default")
      (node (ref "5VOUT") (pin "1") (pinfunction "1_1") (pintype "passive"))
      (node (ref "FB7") (pin "2") (pinfunction "2_2") (pintype "passive"))
    )
    (net (code "46") (name "Net-(5VOUT-Pad2)") (class "Default")
      (node (ref "5VOUT") (pin "2") (pinfunction "2_2") (pintype "passive"))
      (node (ref "FB6") (pin "2") (pinfunction "2_2") (pintype "passive"))
    )
    (net (code "47") (name "Net-(5VREG-EN)") (class "Default")
      (node (ref "5VREG") (pin "P$3") (pinfunction "EN_P$3") (pintype "input"))
      (node (ref "D1") (pin "C") (pinfunction "C_C") (pintype "passive"))
      (node (ref "Q3") (pin "3") (pinfunction "D_3") (pintype "passive"))
      (node (ref "R402") (pin "2") (pinfunction "2_2") (pintype "passive"))
      (node (ref "R403") (pin "1") (pinfunction "1_1") (pintype "passive"))
    )
    (net (code "48") (name "Net-(5VREG-FB)") (class "Default")
      (node (ref "5VREG") (pin "P$5") (pinfunction "FB_P$5") (pintype "passive"))
      (node (ref "R405") (pin "2") (pinfunction "2_2") (pintype "passive"))
      (node (ref "R406") (pin "1") (pinfunction "1_1") (pintype "passive"))
    )
    (net (code "49") (name "Net-(5VREG-SS)") (class "Default")
      (node (ref "5VREG") (pin "P$6") (pinfunction "SS_P$6") (pintype "passive"))
      (node (ref "C401") (pin "1") (pinfunction "1_1") (pintype "passive"))
    )
    (net (code "50") (name "Net-(ADC-CH0+)") (class "Default")
      (node (ref "ADC") (pin "1") (pinfunction "CH0+_1") (pintype "input"))
      (node (ref "CF310") (pin "1") (pinfunction "1_1") (pintype "passive"))
      (node (ref "R320") (pin "2") (pinfunction "2_2") (pintype "passive"))
    )
    (net (code "51") (name "Net-(ADC-CH0-)") (class "Default")
      (node (ref "ADC") (pin "2") (pinfunction "CH0-_2") (pintype "input"))
      (node (ref "ADC") (pin "5") (pinfunction "CH1-_5") (pintype "input"))
      (node (ref "CF311") (pin "1") (pinfunction "1_1") (pintype "passive"))
      (node (ref "R321") (pin "1") (pinfunction "1_1") (pintype "passive"))
    )
    (net (code "52") (name "Net-(ADC-CH1+)") (class "Default")
      (node (ref "ADC") (pin "4") (pinfunction "CH1+_4") (pintype "input"))
      (node (ref "CF305") (pin "1") (pinfunction "1_1") (pintype "passive"))
      (node (ref "R310") (pin "2") (pinfunction "2_2") (pintype "passive"))
    )
    (net (code "53") (name "Net-(C201-Pad2)") (class "Default")
      (node (ref "C201") (pin "2") (pinfunction "2_2") (pintype "passive"))
      (node (ref "R201") (pin "1") (pinfunction "1_1") (pintype "passive"))
    )
    (net (code "54") (name "Net-(C204-Pad1)") (class "Default")
      (node (ref "C204") (pin "1") (pinfunction "1_1") (pintype "passive"))
      (node (ref "R205") (pin "1") (pinfunction "1_1") (pintype "passive"))
    )
    (net (code "55") (name "Net-(C205-1)") (class "Default")
      (node (ref "C205") (pin "P$1") (pinfunction "1_P$1") (pintype "passive"))
      (node (ref "LF1") (pin "P$1") (pinfunction "1_P$1") (pintype "passive"))
      (node (ref "R207") (pin "2") (pinfunction "2_2") (pintype "passive"))
      (node (ref "T2") (pin "P$5") (pinfunction "1_P$5") (pintype "passive"))
    )
    (net (code "56") (name "Net-(C206-1)") (class "Default")
      (node (ref "C206") (pin "P$1") (pinfunction "1_P$1") (pintype "passive"))
      (node (ref "C220") (pin "2") (pinfunction "2_2") (pintype "passive"))
      (node (ref "LF1") (pin "P$2") (pinfunction "2_P$2") (pintype "passive"))
      (node (ref "R209") (pin "2") (pinfunction "2_2") (pintype "passive"))
    )
    (net (code "57") (name "Net-(C207-1)") (class "Default")
      (node (ref "C207") (pin "P$1") (pinfunction "1_P$1") (pintype "passive"))
      (node (ref "LF2") (pin "P$1") (pinfunction "1_P$1") (pintype "passive"))
      (node (ref "R208") (pin "2") (pinfunction "2_2") (pintype "passive"))
      (node (ref "T1") (pin "P$5") (pinfunction "1_P$5") (pintype "passive"))
    )
    (net (code "58") (name "Net-(C208-1)") (class "Default")
      (node (ref "C208") (pin "P$1") (pinfunction "1_P$1") (pintype "passive"))
      (node (ref "C219") (pin "2") (pinfunction "2_2") (pintype "passive"))
      (node (ref "LF2") (pin "P$2") (pinfunction "2_P$2") (pintype "passive"))
      (node (ref "R210") (pin "2") (pinfunction "2_2") (pintype "passive"))
    )
    (net (code "59") (name "Net-(C209-Pad1)") (class "Default")
      (node (ref "C209") (pin "1") (pinfunction "1_1") (pintype "passive"))
      (node (ref "R215") (pin "2") (pinfunction "2_2") (pintype "passive"))
    )
    (net (code "60") (name "Net-(C210-Pad1)") (class "Default")
      (node (ref "C210") (pin "1") (pinfunction "1_1") (pintype "passive"))
      (node (ref "R219") (pin "2") (pinfunction "2_2") (pintype "passive"))
    )
    (net (code "61") (name "Net-(C211-Pad1)") (class "Default")
      (node (ref "C211") (pin "1") (pinfunction "1_1") (pintype "passive"))
      (node (ref "TX0") (pin "1") (pinfunction "1_1") (pintype "passive"))
    )
    (net (code "62") (name "Net-(C211-Pad2)") (class "Default")
      (node (ref "C211") (pin "2") (pinfunction "2_2") (pintype "passive"))
      (node (ref "R216") (pin "1") (pinfunction "1_1") (pintype "passive"))
    )
    (net (code "63") (name "Net-(C212-Pad2)") (class "Default")
      (node (ref "C212") (pin "2") (pinfunction "2_2") (pintype "passive"))
      (node (ref "R220") (pin "1") (pinfunction "1_1") (pintype "passive"))
    )
    (net (code "64") (name "Net-(C213-Pad1)") (class "Default")
      (node (ref "C213") (pin "1") (pinfunction "1_1") (pintype "passive"))
      (node (ref "LO0") (pin "1") (pinfunction "1_1") (pintype "passive"))
    )
    (net (code "65") (name "Net-(C213-Pad2)") (class "Default")
      (node (ref "C213") (pin "2") (pinfunction "2_2") (pintype "passive"))
      (node (ref "R221") (pin "1") (pinfunction "1_1") (pintype "passive"))
    )
    (net (code "66") (name "Net-(C214-Pad1)") (class "Default")
      (node (ref "C214") (pin "1") (pinfunction "1_1") (pintype "passive"))
      (node (ref "R226") (pin "2") (pinfunction "2_2") (pintype "passive"))
    )
    (net (code "67") (name "Net-(C215-Pad1)") (class "Default")
      (node (ref "C215") (pin "1") (pinfunction "1_1") (pintype "passive"))
      (node (ref "R230") (pin "2") (pinfunction "2_2") (pintype "passive"))
    )
    (net (code "68") (name "Net-(C216-Pad1)") (class "Default")
      (node (ref "C216") (pin "1") (pinfunction "1_1") (pintype "passive"))
      (node (ref "TX1") (pin "1") (pinfunction "1_1") (pintype "passive"))
    )
    (net (code "69") (name "Net-(C216-Pad2)") (class "Default")
      (node (ref "C216") (pin "2") (pinfunction "2_2") (pintype "passive"))
      (node (ref "R227") (pin "1") (pinfunction "1_1") (pintype "passive"))
    )
    (net (code "70") (name "Net-(C217-Pad2)") (class "Default")
      (node (ref "C217") (pin "2") (pinfunction "2_2") (pintype "passive"))
      (node (ref "R232") (pin "1") (pinfunction "1_1") (pintype "passive"))
    )
    (net (code "71") (name "Net-(C218-Pad1)") (class "Default")
      (node (ref "C218") (pin "1") (pinfunction "1_1") (pintype "passive"))
      (node (ref "LO1") (pin "1") (pinfunction "1_1") (pintype "passive"))
    )
    (net (code "72") (name "Net-(C218-Pad2)") (class "Default")
      (node (ref "C218") (pin "2") (pinfunction "2_2") (pintype "passive"))
      (node (ref "R233") (pin "1") (pinfunction "1_1") (pintype "passive"))
    )
    (net (code "73") (name "Net-(C219-Pad1)") (class "Default")
      (node (ref "C219") (pin "1") (pinfunction "1_1") (pintype "passive"))
      (node (ref "R222") (pin "2") (pinfunction "2_2") (pintype "passive"))
      (node (ref "R223") (pin "1") (pinfunction "1_1") (pintype "passive"))
      (node (ref "R224") (pin "2") (pinfunction "2_2") (pintype "passive"))
      (node (ref "R228") (pin "2") (pinfunction "2_2") (pintype "passive"))
    )
    (net (code "74") (name "Net-(C220-Pad1)") (class "Default")
      (node (ref "C220") (pin "1") (pinfunction "1_1") (pintype "passive"))
      (node (ref "R211") (pin "2") (pinfunction "2_2") (pintype "passive"))
      (node (ref "R212") (pin "1") (pinfunction "1_1") (pintype "passive"))
      (node (ref "R213") (pin "2") (pinfunction "2_2") (pintype "passive"))
      (node (ref "R217") (pin "2") (pinfunction "2_2") (pintype "passive"))
    )
    (net (code "75") (name "Net-(CF301-Pad1)") (class "Default")
      (node (ref "CF301") (pin "1") (pinfunction "1_1") (pintype "passive"))
      (node (ref "R303") (pin "2") (pinfunction "2_2") (pintype "passive"))
      (node (ref "R304") (pin "1") (pinfunction "1_1") (pintype "passive"))
    )
    (net (code "76") (name "Net-(CF304-Pad2)") (class "Default")
      (node (ref "CF304") (pin "2") (pinfunction "2_2") (pintype "passive"))
      (node (ref "R306") (pin "2") (pinfunction "2_2") (pintype "passive"))
      (node (ref "R307") (pin "1") (pinfunction "1_1") (pintype "passive"))
    )
    (net (code "77") (name "Net-(CF306-Pad1)") (class "Default")
      (node (ref "CF306") (pin "1") (pinfunction "1_1") (pintype "passive"))
      (node (ref "R313") (pin "2") (pinfunction "2_2") (pintype "passive"))
      (node (ref "R314") (pin "1") (pinfunction "1_1") (pintype "passive"))
    )
    (net (code "78") (name "Net-(CF309-Pad2)") (class "Default")
      (node (ref "CF309") (pin "2") (pinfunction "2_2") (pintype "passive"))
      (node (ref "R316") (pin "2") (pinfunction "2_2") (pintype "passive"))
      (node (ref "R317") (pin "1") (pinfunction "1_1") (pintype "passive"))
    )
    (net (code "79") (name "Net-(CH0/I-Pad1)") (class "Default")
      (node (ref "CH0/I") (pin "1") (pinfunction "1_1") (pintype "passive"))
      (node (ref "R327") (pin "1") (pinfunction "1_1") (pintype "passive"))
    )
    (net (code "80") (name "Net-(CH1/Q-Pad1)") (class "Default")
      (node (ref "CH1/Q") (pin "1") (pinfunction "1_1") (pintype "passive"))
      (node (ref "R326") (pin "1") (pinfunction "1_1") (pintype "passive"))
    )
    (net (code "81") (name "Net-(DDSA-LOOP_FILTER)") (class "Default")
      (node (ref "DDS") (pin "27") (pinfunction "LOOP_FILTER_27") (pintype "passive"))
      (node (ref "R205") (pin "2") (pinfunction "2_2") (pintype "passive"))
    )
    (net (code "82") (name "Net-(DDSA-REF_CLK)") (class "Default")
      (node (ref "C202") (pin "1") (pinfunction "1_1") (pintype "passive"))
      (node (ref "DDS") (pin "23") (pinfunction "REF_CLK_23") (pintype "input"))
    )
    (net (code "83") (name "Net-(DDSA-SYNC_CLK)") (class "Default")
      (node (ref "DDS") (pin "54") (pinfunction "SYNC_CLK_54") (pintype "output"))
      (node (ref "SYNC") (pin "TP") (pinfunction "TP_TP") (pintype "input"))
    )
    (net (code "84") (name "Net-(DDSA-~{REF_CLK})") (class "Default")
      (node (ref "C203") (pin "1") (pinfunction "1_1") (pintype "passive"))
      (node (ref "DDS") (pin "22") (pinfunction "~{REF_CLK}_22") (pintype "input"))
    )
    (net (code "85") (name "Net-(DDSB-CH0_IO)") (class "Default")
      (node (ref "DDS") (pin "8") (pinfunction "CH0_IO_8") (pintype "output"))
      (node (ref "T2") (pin "P$1") (pinfunction "6_P$1") (pintype "passive"))
    )
    (net (code "86") (name "Net-(DDSB-CH1_IO)") (class "Default")
      (node (ref "DDS") (pin "13") (pinfunction "CH1_IO_13") (pintype "output"))
      (node (ref "T1") (pin "P$1") (pinfunction "6_P$1") (pintype "passive"))
    )
    (net (code "87") (name "Net-(DDSB-RSET)") (class "Default")
      (node (ref "DDS") (pin "17") (pinfunction "RSET_17") (pintype "passive"))
      (node (ref "R206") (pin "2") (pinfunction "2_2") (pintype "passive"))
    )
    (net (code "88") (name "Net-(DDSB-~{CH0_IO})") (class "Default")
      (node (ref "DDS") (pin "9") (pinfunction "~{CH0_IO}_9") (pintype "output"))
      (node (ref "T2") (pin "P$3") (pinfunction "4_P$3") (pintype "passive"))
    )
    (net (code "89") (name "Net-(DDSB-~{CH1_IO})") (class "Default")
      (node (ref "DDS") (pin "14") (pinfunction "~{CH1_IO}_14") (pintype "output"))
      (node (ref "T1") (pin "P$3") (pinfunction "4_P$3") (pintype "passive"))
    )
    (net (code "90") (name "Net-(FTDI-3V3OUT)") (class "Default")
      (node (ref "CB118") (pin "1") (pinfunction "1_1") (pintype "passive"))
      (node (ref "CB119") (pin "1") (pinfunction "1_1") (pintype "passive"))
      (node (ref "CB120") (pin "1") (pinfunction "1_1") (pintype "passive"))
      (node (ref "FTDI") (pin "17") (pinfunction "3V3OUT_17") (pintype "output"))
      (node (ref "FTDI") (pin "4") (pinfunction "VCCIO_4") (pintype "power_in"))
      (node (ref "R111") (pin "1") (pinfunction "1_1") (pintype "passive"))
      (node (ref "R112") (pin "1") (pinfunction "1_1") (pintype "passive"))
    )
    (net (code "91") (name "Net-(FTDI-CBUS0)") (class "Default")
      (node (ref "FTDI") (pin "23") (pinfunction "CBUS0_23") (pintype "bidirectional"))
      (node (ref "L_RX") (pin "C") (pinfunction "C_C") (pintype "passive"))
    )
    (net (code "92") (name "Net-(FTDI-CBUS1)") (class "Default")
      (node (ref "FTDI") (pin "22") (pinfunction "CBUS1_22") (pintype "bidirectional"))
      (node (ref "L_TX") (pin "C") (pinfunction "C_C") (pintype "passive"))
    )
    (net (code "93") (name "Net-(FTDI-RESET#)") (class "Default")
      (node (ref "FTDI") (pin "19") (pinfunction "RESET#_19") (pintype "input"))
      (node (ref "R113") (pin "1") (pinfunction "1_1") (pintype "passive"))
      (node (ref "R114") (pin "1") (pinfunction "1_1") (pintype "passive"))
    )
    (net (code "94") (name "Net-(FTDI-USBDM)") (class "Default")
      (node (ref "FTDI") (pin "16") (pinfunction "USBDM_16") (pintype "bidirectional"))
      (node (ref "R116") (pin "1") (pinfunction "1_1") (pintype "passive"))
    )
    (net (code "95") (name "Net-(FTDI-USBDP)") (class "Default")
      (node (ref "FTDI") (pin "15") (pinfunction "USBDP_15") (pintype "bidirectional"))
      (node (ref "R115") (pin "1") (pinfunction "1_1") (pintype "passive"))
    )
    (net (code "96") (name "Net-(GCLK0-PP)") (class "Default")
      (node (ref "GCLK0") (pin "TP") (pinfunction "PP_TP") (pintype "input"))
      (node (ref "MCU") (pin "67") (pinfunction "PC19/PWM-PWML[2]/SCIF-GCLK[0]/EBI-DATA[0]/IISC-IMCK/USART3-CTS_67") (pintype "bidirectional"))
    )
    (net (code "97") (name "Net-(GCLK1-PP)") (class "Default")
      (node (ref "GCLK1") (pin "TP") (pinfunction "PP_TP") (pintype "input"))
      (node (ref "MCU") (pin "68") (pinfunction "PC20/PWM-PWMH[2]/SCIF-GCLK[1]/EBI-DATA[1]/IISC-ISCK/USART3-RTS_68") (pintype "bidirectional"))
    )
    (net (code "98") (name "Net-(JP1-Pad1)") (class "Default")
      (node (ref "JP1") (pin "1") (pinfunction "1_1") (pintype "passive"))
      (node (ref "R105") (pin "1") (pinfunction "1_1") (pintype "passive"))
    )
    (net (code "99") (name "Net-(JP1-Pad3)") (class "Default")
      (node (ref "JP1") (pin "3") (pinfunction "3_3") (pintype "passive"))
      (node (ref "R104") (pin "1") (pinfunction "1_1") (pintype "passive"))
    )
    (net (code "100") (name "Net-(L_RX-PadA)") (class "Default")
      (node (ref "L_RX") (pin "A") (pinfunction "A_A") (pintype "passive"))
      (node (ref "R111") (pin "2") (pinfunction "2_2") (pintype "passive"))
    )
    (net (code "101") (name "Net-(L_TX-PadA)") (class "Default")
      (node (ref "L_TX") (pin "A") (pinfunction "A_A") (pintype "passive"))
      (node (ref "R112") (pin "2") (pinfunction "2_2") (pintype "passive"))
    )
    (net (code "102") (name "Net-(MCU-ADCREFN{slash}PA18)") (class "Default")
      (node (ref "CB124") (pin "2") (pinfunction "2_2") (pintype "passive"))
      (node (ref "MCU") (pin "24") (pinfunction "ADCREFN/PA18_24") (pintype "bidirectional"))
    )
    (net (code "103") (name "Net-(MCU-ADCREFP{slash}PA17)") (class "Default")
      (node (ref "CB124") (pin "1") (pinfunction "1_1") (pintype "passive"))
      (node (ref "MCU") (pin "23") (pinfunction "ADCREFP/PA17_23") (pintype "bidirectional"))
    )
    (net (code "104") (name "Net-(MCU-DM)") (class "Default")
      (node (ref "MCU") (pin "34") (pinfunction "VBUS_34") (pintype "bidirectional"))
      (node (ref "MCU") (pin "35") (pinfunction "DM_35") (pintype "bidirectional"))
      (node (ref "MCU") (pin "36") (pinfunction "DP_36") (pintype "bidirectional"))
      (node (ref "R120") (pin "2") (pinfunction "2_2") (pintype "passive"))
    )
    (net (code "105") (name "Net-(MCU-PD27{slash}USART0-TXD{slash}CANIF-RXLINE[0]{slash}EBI-NCS[1]{slash}TC0-A0{slash}MACB-RX_ER)") (class "Default")
      (node (ref "LCD") (pin "4") (pinfunction "4_4") (pintype "passive"))
      (node (ref "MCU") (pin "92") (pinfunction "PD27/USART0-TXD/CANIF-RXLINE[0]/EBI-NCS[1]/TC0-A0/MACB-RX_ER_92") (pintype "bidirectional"))
    )
    (net (code "106") (name "Net-(MCU-PD28{slash}USART0-RXD{slash}CANIF-TXLINE[0]{slash}EBI-NCS[2]{slash}TC0-B0{slash}MACB-RC_DV)") (class "Default")
      (node (ref "LCD") (pin "2") (pinfunction "2_2") (pintype "passive"))
      (node (ref "MCU") (pin "93") (pinfunction "PD28/USART0-RXD/CANIF-TXLINE[0]/EBI-NCS[2]/TC0-B0/MACB-RC_DV_93") (pintype "bidirectional"))
    )
    (net (code "107") (name "Net-(MCU-TCK{slash}CANIF-TXLINE[1]{slash}PA00)") (class "Default")
      (node (ref "JTAG") (pin "1") (pinfunction "1_1") (pintype "passive"))
      (node (ref "MCU") (pin "1") (pinfunction "TCK/CANIF-TXLINE[1]/PA00_1") (pintype "bidirectional"))
      (node (ref "R101") (pin "1") (pinfunction "1_1") (pintype "passive"))
    )
    (net (code "108") (name "Net-(MCU-TDI{slash}CANIF-RXLINE[1]{slash}PEVC-PAD_EVT[0]{slash}PA01)") (class "Default")
      (node (ref "JTAG") (pin "9") (pinfunction "9_9") (pintype "passive"))
      (node (ref "MCU") (pin "2") (pinfunction "TDI/CANIF-RXLINE[1]/PEVC-PAD_EVT[0]/PA01_2") (pintype "bidirectional"))
    )
    (net (code "109") (name "Net-(MCU-TDO{slash}SCIF-GLK[0]{slash}PEVC-PAD_EVT[1]{slash}PA02)") (class "Default")
      (node (ref "JTAG") (pin "3") (pinfunction "3_3") (pintype "passive"))
      (node (ref "MCU") (pin "3") (pinfunction "TDO/SCIF-GLK[0]/PEVC-PAD_EVT[1]/PA02_3") (pintype "bidirectional"))
    )
    (net (code "110") (name "Net-(MCU-TMS{slash}SCIF-GCLK[1]{slash}EIC-EXINT[1]{slash}PA03)") (class "Default")
      (node (ref "JTAG") (pin "5") (pinfunction "5_5") (pintype "passive"))
      (node (ref "MCU") (pin "4") (pinfunction "TMS/SCIF-GCLK[1]/EIC-EXINT[1]/PA03_4") (pintype "bidirectional"))
    )
    (net (code "111") (name "Net-(MCU-~{RESET})") (class "Default")
      (node (ref "CB123") (pin "1") (pinfunction "1_1") (pintype "passive"))
      (node (ref "JTAG") (pin "6") (pinfunction "6_6") (pintype "passive"))
      (node (ref "MCU") (pin "98") (pinfunction "~{RESET}_98") (pintype "input"))
      (node (ref "R102") (pin "2") (pinfunction "2_2") (pintype "passive"))
      (node (ref "R103") (pin "1") (pinfunction "1_1") (pintype "passive"))
    )
    (net (code "112") (name "Net-(MX0-IF)") (class "Default")
      (node (ref "MX0") (pin "P$2") (pinfunction "IF_P$2") (pintype "passive"))
      (node (ref "R312") (pin "2") (pinfunction "2_2") (pintype "passive"))
      (node (ref "R313") (pin "1") (pinfunction "1_1") (pintype "passive"))
    )
    (net (code "113") (name "Net-(MX0-RFN)") (class "Default")
      (node (ref "MX0") (pin "P$4") (pinfunction "RFN_P$4") (pintype "passive"))
      (node (ref "R311") (pin "2") (pinfunction "2_2") (pintype "passive"))
      (node (ref "RFIN0") (pin "2") (pinfunction "GND1_2") (pintype "power_in"))
      (node (ref "RFIN0") (pin "3") (pinfunction "GND2_3") (pintype "power_in"))
    )
    (net (code "114") (name "Net-(MX0-RFP)") (class "Default")
      (node (ref "MX0") (pin "P$3") (pinfunction "RFP_P$3") (pintype "passive"))
      (node (ref "RFIN0") (pin "1") (pinfunction "1_1") (pintype "passive"))
    )
    (net (code "115") (name "Net-(MX1-IF)") (class "Default")
      (node (ref "MX1") (pin "P$2") (pinfunction "IF_P$2") (pintype "passive"))
      (node (ref "R302") (pin "2") (pinfunction "2_2") (pintype "passive"))
      (node (ref "R303") (pin "1") (pinfunction "1_1") (pintype "passive"))
    )
    (net (code "116") (name "Net-(MX1-RFN)") (class "Default")
      (node (ref "MX1") (pin "P$4") (pinfunction "RFN_P$4") (pintype "passive"))
      (node (ref "R301") (pin "2") (pinfunction "2_2") (pintype "passive"))
      (node (ref "RFIN1") (pin "2") (pinfunction "GND1_2") (pintype "power_in"))
      (node (ref "RFIN1") (pin "3") (pinfunction "GND2_3") (pintype "power_in"))
    )
    (net (code "117") (name "Net-(MX1-RFP)") (class "Default")
      (node (ref "MX1") (pin "P$3") (pinfunction "RFP_P$3") (pintype "passive"))
      (node (ref "RFIN1") (pin "1") (pinfunction "1_1") (pintype "passive"))
    )
    (net (code "118") (name "Net-(OP1A-+IN)") (class "Default")
      (node (ref "OP1") (pin "3") (pinfunction "+IN_3") (pintype "input"))
      (node (ref "R224") (pin "1") (pinfunction "1_1") (pintype "passive"))
    )
    (net (code "119") (name "Net-(OP1A--IN)") (class "Default")
      (node (ref "OP1") (pin "2") (pinfunction "-IN_2") (pintype "input"))
      (node (ref "R225") (pin "2") (pinfunction "2_2") (pintype "passive"))
      (node (ref "R226") (pin "1") (pinfunction "1_1") (pintype "passive"))
    )
    (net (code "120") (name "Net-(OP1A-OUT)") (class "Default")
      (node (ref "OP1") (pin "1") (pinfunction "OUT_1") (pintype "output"))
      (node (ref "R225") (pin "1") (pinfunction "1_1") (pintype "passive"))
      (node (ref "R227") (pin "2") (pinfunction "2_2") (pintype "passive"))
    )
    (net (code "121") (name "Net-(OP1B-+IN)") (class "Default")
      (node (ref "OP1") (pin "5") (pinfunction "+IN_5") (pintype "input"))
      (node (ref "R228") (pin "1") (pinfunction "1_1") (pintype "passive"))
    )
    (net (code "122") (name "Net-(OP1B--IN)") (class "Default")
      (node (ref "OP1") (pin "6") (pinfunction "-IN_6") (pintype "input"))
      (node (ref "R230") (pin "1") (pinfunction "1_1") (pintype "passive"))
      (node (ref "R231") (pin "2") (pinfunction "2_2") (pintype "passive"))
    )
    (net (code "123") (name "Net-(OP1B-OUT)") (class "Default")
      (node (ref "OP1") (pin "7") (pinfunction "OUT_7") (pintype "output"))
      (node (ref "R231") (pin "1") (pinfunction "1_1") (pintype "passive"))
      (node (ref "R232") (pin "2") (pinfunction "2_2") (pintype "passive"))
      (node (ref "R233") (pin "2") (pinfunction "2_2") (pintype "passive"))
    )
    (net (code "124") (name "Net-(OP1C-V+)") (class "Default")
      (node (ref "CB215") (pin "1") (pinfunction "1_1") (pintype "passive"))
      (node (ref "CB216") (pin "1") (pinfunction "1_1") (pintype "passive"))
      (node (ref "FB2") (pin "2") (pinfunction "2_2") (pintype "passive"))
      (node (ref "OP1") (pin "8") (pinfunction "V+_8") (pintype "power_in"))
      (node (ref "R223") (pin "2") (pinfunction "2_2") (pintype "passive"))
    )
    (net (code "125") (name "Net-(OP2A-+IN)") (class "Default")
      (node (ref "OP2") (pin "3") (pinfunction "+IN_3") (pintype "input"))
      (node (ref "R213") (pin "1") (pinfunction "1_1") (pintype "passive"))
    )
    (net (code "126") (name "Net-(OP2A--IN)") (class "Default")
      (node (ref "OP2") (pin "2") (pinfunction "-IN_2") (pintype "input"))
      (node (ref "R214") (pin "2") (pinfunction "2_2") (pintype "passive"))
      (node (ref "R215") (pin "1") (pinfunction "1_1") (pintype "passive"))
    )
    (net (code "127") (name "Net-(OP2A-OUT)") (class "Default")
      (node (ref "OP2") (pin "1") (pinfunction "OUT_1") (pintype "output"))
      (node (ref "R214") (pin "1") (pinfunction "1_1") (pintype "passive"))
      (node (ref "R216") (pin "2") (pinfunction "2_2") (pintype "passive"))
    )
    (net (code "128") (name "Net-(OP2B-+IN)") (class "Default")
      (node (ref "OP2") (pin "5") (pinfunction "+IN_5") (pintype "input"))
      (node (ref "R217") (pin "1") (pinfunction "1_1") (pintype "passive"))
    )
    (net (code "129") (name "Net-(OP2B--IN)") (class "Default")
      (node (ref "OP2") (pin "6") (pinfunction "-IN_6") (pintype "input"))
      (node (ref "R218") (pin "2") (pinfunction "2_2") (pintype "passive"))
      (node (ref "R219") (pin "1") (pinfunction "1_1") (pintype "passive"))
    )
    (net (code "130") (name "Net-(OP2B-OUT)") (class "Default")
      (node (ref "OP2") (pin "7") (pinfunction "OUT_7") (pintype "output"))
      (node (ref "R218") (pin "1") (pinfunction "1_1") (pintype "passive"))
      (node (ref "R220") (pin "2") (pinfunction "2_2") (pintype "passive"))
      (node (ref "R221") (pin "2") (pinfunction "2_2") (pintype "passive"))
    )
    (net (code "131") (name "Net-(OP2C-V+)") (class "Default")
      (node (ref "CB213") (pin "1") (pinfunction "1_1") (pintype "passive"))
      (node (ref "CB214") (pin "1") (pinfunction "1_1") (pintype "passive"))
      (node (ref "FB1") (pin "2") (pinfunction "2_2") (pintype "passive"))
      (node (ref "OP2") (pin "8") (pinfunction "V+_8") (pintype "power_in"))
      (node (ref "R212") (pin "2") (pinfunction "2_2") (pintype "passive"))
    )
    (net (code "132") (name "Net-(OP3A--IN)") (class "Default")
      (node (ref "CF302") (pin "2") (pinfunction "2_2") (pintype "passive"))
      (node (ref "OP3") (pin "2") (pinfunction "-IN_2") (pintype "input"))
      (node (ref "R304") (pin "2") (pinfunction "2_2") (pintype "passive"))
      (node (ref "R305") (pin "1") (pinfunction "1_1") (pintype "passive"))
    )
    (net (code "133") (name "Net-(OP3A-OUT)") (class "Default")
      (node (ref "CF302") (pin "1") (pinfunction "1_1") (pintype "passive"))
      (node (ref "OP3") (pin "1") (pinfunction "OUT_1") (pintype "output"))
      (node (ref "R305") (pin "2") (pinfunction "2_2") (pintype "passive"))
      (node (ref "R306") (pin "1") (pinfunction "1_1") (pintype "passive"))
    )
    (net (code "134") (name "Net-(OP3B-+IN)") (class "Default")
      (node (ref "CF303") (pin "1") (pinfunction "1_1") (pintype "passive"))
      (node (ref "OP3") (pin "5") (pinfunction "+IN_5") (pintype "input"))
      (node (ref "R307") (pin "2") (pinfunction "2_2") (pintype "passive"))
    )
    (net (code "135") (name "Net-(OP3B--IN)") (class "Default")
      (node (ref "OP3") (pin "6") (pinfunction "-IN_6") (pintype "input"))
      (node (ref "R308") (pin "1") (pinfunction "1_1") (pintype "passive"))
      (node (ref "R309") (pin "2") (pinfunction "2_2") (pintype "passive"))
    )
    (net (code "136") (name "Net-(OP3B-OUT)") (class "Default")
      (node (ref "CF304") (pin "1") (pinfunction "1_1") (pintype "passive"))
      (node (ref "OP3") (pin "7") (pinfunction "OUT_7") (pintype "output"))
      (node (ref "R309") (pin "1") (pinfunction "1_1") (pintype "passive"))
      (node (ref "R310") (pin "1") (pinfunction "1_1") (pintype "passive"))
      (node (ref "R326") (pin "2") (pinfunction "2_2") (pintype "passive"))
      (node (ref "TP9") (pin "TP") (pinfunction "TP_TP") (pintype "input"))
    )
    (net (code "137") (name "Net-(OP3C-+IN)") (class "Default")
      (node (ref "CF308") (pin "1") (pinfunction "1_1") (pintype "passive"))
      (node (ref "OP3") (pin "10") (pinfunction "+IN_10") (pintype "input"))
      (node (ref "R317") (pin "2") (pinfunction "2_2") (pintype "passive"))
    )
    (net (code "138") (name "Net-(OP3C--IN)") (class "Default")
      (node (ref "OP3") (pin "9") (pinfunction "-IN_9") (pintype "input"))
      (node (ref "R318") (pin "1") (pinfunction "1_1") (pintype "passive"))
      (node (ref "R319") (pin "2") (pinfunction "2_2") (pintype "passive"))
    )
    (net (code "139") (name "Net-(OP3C-OUT)") (class "Default")
      (node (ref "CF309") (pin "1") (pinfunction "1_1") (pintype "passive"))
      (node (ref "OP3") (pin "8") (pinfunction "OUT_8") (pintype "output"))
      (node (ref "R319") (pin "1") (pinfunction "1_1") (pintype "passive"))
      (node (ref "R320") (pin "1") (pinfunction "1_1") (pintype "passive"))
      (node (ref "R327") (pin "2") (pinfunction "2_2") (pintype "passive"))
      (node (ref "TP6") (pin "TP") (pinfunction "TP_TP") (pintype "input"))
    )
    (net (code "140") (name "Net-(OP3D--IN)") (class "Default")
      (node (ref "CF307") (pin "2") (pinfunction "2_2") (pintype "passive"))
      (node (ref "OP3") (pin "13") (pinfunction "-IN_13") (pintype "input"))
      (node (ref "R314") (pin "2") (pinfunction "2_2") (pintype "passive"))
      (node (ref "R315") (pin "1") (pinfunction "1_1") (pintype "passive"))
    )
    (net (code "141") (name "Net-(OP3D-OUT)") (class "Default")
      (node (ref "CF307") (pin "1") (pinfunction "1_1") (pintype "passive"))
      (node (ref "OP3") (pin "14") (pinfunction "OUT_14") (pintype "output"))
      (node (ref "R315") (pin "2") (pinfunction "2_2") (pintype "passive"))
      (node (ref "R316") (pin "1") (pinfunction "1_1") (pintype "passive"))
    )
    (net (code "142") (name "Net-(OP4A-+IN)") (class "Default")
      (node (ref "CB309") (pin "1") (pinfunction "1_1") (pintype "passive"))
      (node (ref "OP4") (pin "3") (pinfunction "+IN_3") (pintype "input"))
      (node (ref "R322") (pin "1") (pinfunction "1_1") (pintype "passive"))
      (node (ref "R323") (pin "1") (pinfunction "1_1") (pintype "passive"))
    )
    (net (code "143") (name "Net-(PUMP-C+)") (class "Default")
      (node (ref "C406") (pin "2") (pinfunction "2_2") (pintype "passive"))
      (node (ref "CF") (pin "1") (pinfunction "1_1") (pintype "passive"))
      (node (ref "PUMP") (pin "2") (pinfunction "C+_2") (pintype "passive"))
    )
    (net (code "144") (name "Net-(PUMP-C-)") (class "Default")
      (node (ref "CF") (pin "2") (pinfunction "2_2") (pintype "passive"))
      (node (ref "PUMP") (pin "4") (pinfunction "C-_4") (pintype "passive"))
    )
    (net (code "145") (name "Net-(PUMP-FB{slash}~{SHDN})") (class "Default")
      (node (ref "PUMP") (pin "1") (pinfunction "FB/~{SHDN}_1") (pintype "input"))
      (node (ref "Q1") (pin "3") (pinfunction "D_3") (pintype "passive"))
      (node (ref "R411") (pin "2") (pinfunction "2_2") (pintype "passive"))
      (node (ref "R416") (pin "1") (pinfunction "1_1") (pintype "passive"))
      (node (ref "R417") (pin "1") (pinfunction "1_1") (pintype "passive"))
    )
    (net (code "146") (name "Net-(PUMP-OSC)") (class "Default")
      (node (ref "C406") (pin "1") (pinfunction "1_1") (pintype "passive"))
      (node (ref "PUMP") (pin "7") (pinfunction "OSC_7") (pintype "passive"))
    )
    (net (code "147") (name "Net-(PUMP-V+)") (class "Default")
      (node (ref "CB410") (pin "1") (pinfunction "1_1") (pintype "passive"))
      (node (ref "FB5") (pin "1") (pinfunction "1_1") (pintype "passive"))
      (node (ref "PUMP") (pin "8") (pinfunction "V+_8") (pintype "power_in"))
      (node (ref "R411") (pin "1") (pinfunction "1_1") (pintype "passive"))
    )
    (net (code "148") (name "Net-(PUMP-VOUT)") (class "Default")
      (node (ref "-12VOUT") (pin "1") (pinfunction "1_1") (pintype "passive"))
      (node (ref "CB411") (pin "1") (pinfunction "1_1") (pintype "passive"))
      (node (ref "PUMP") (pin "5") (pinfunction "VOUT_5") (pintype "power_in"))
      (node (ref "R417") (pin "2") (pinfunction "2_2") (pintype "passive"))
    )
    (net (code "149") (name "Net-(PUMP-VREF)") (class "Default")
      (node (ref "CB1") (pin "1") (pinfunction "1_1") (pintype "passive"))
      (node (ref "PUMP") (pin "6") (pinfunction "VREF_6") (pintype "input"))
      (node (ref "R416") (pin "2") (pinfunction "2_2") (pintype "passive"))
    )
    (net (code "150") (name "Net-(Q2-D)") (class "Default")
      (node (ref "FUSE") (pin "1") (pinfunction "1_1") (pintype "passive"))
      (node (ref "Q2") (pin "3") (pinfunction "D_3") (pintype "passive"))
    )
    (net (code "151") (name "Net-(Q2-G)") (class "Default")
      (node (ref "Q2") (pin "1") (pinfunction "G_1") (pintype "passive"))
      (node (ref "R401") (pin "2") (pinfunction "2_2") (pintype "passive"))
      (node (ref "Z1") (pin "A") (pinfunction "A_A") (pintype "passive"))
    )
    (net (code "152") (name "Net-(R103-Pad2)") (class "Default")
      (node (ref "R103") (pin "2") (pinfunction "2_2") (pintype "passive"))
      (node (ref "RESET") (pin "P$2") (pinfunction "1_P$2") (pintype "passive"))
      (node (ref "RESET") (pin "P$4") (pinfunction "1_P$4") (pintype "passive"))
    )
    (net (code "153") (name "Net-(R107-Pad2)") (class "Default")
      (node (ref "R107") (pin "2") (pinfunction "2_2") (pintype "passive"))
      (node (ref "SD") (pin "DAT2") (pinfunction "DAT2_DAT2") (pintype "bidirectional"))
    )
    (net (code "154") (name "Net-(R114-Pad2)") (class "Default")
      (node (ref "R114") (pin "2") (pinfunction "2_2") (pintype "passive"))
      (node (ref "USB") (pin "1") (pinfunction "1_1") (pintype "input"))
    )
    (net (code "155") (name "Net-(R115-Pad2)") (class "Default")
      (node (ref "R115") (pin "2") (pinfunction "2_2") (pintype "passive"))
      (node (ref "USB") (pin "3") (pinfunction "3_3") (pintype "input"))
    )
    (net (code "156") (name "Net-(R116-Pad2)") (class "Default")
      (node (ref "R116") (pin "2") (pinfunction "2_2") (pintype "passive"))
      (node (ref "USB") (pin "2") (pinfunction "2_2") (pintype "input"))
    )
    (net (code "157") (name "Net-(SD-DAT1{slash}IRQ)") (class "Default")
      (node (ref "R108") (pin "2") (pinfunction "2_2") (pintype "passive"))
      (node (ref "SD") (pin "DAT1") (pinfunction "DAT1/IRQ_DAT1") (pintype "bidirectional"))
    )
    (net (code "158") (name "Net-(T3-1)") (class "Default")
      (node (ref "C202") (pin "2") (pinfunction "2_2") (pintype "passive"))
      (node (ref "R202") (pin "2") (pinfunction "2_2") (pintype "passive"))
      (node (ref "R203") (pin "1") (pinfunction "1_1") (pintype "passive"))
      (node (ref "T3") (pin "P$5") (pinfunction "1_P$5") (pintype "passive"))
    )
    (net (code "159") (name "Net-(T3-3)") (class "Default")
      (node (ref "C201") (pin "1") (pinfunction "1_1") (pintype "passive"))
      (node (ref "T3") (pin "P$4") (pinfunction "3_P$4") (pintype "passive"))
    )
    (net (code "160") (name "Net-(T3-6)") (class "Default")
      (node (ref "C203") (pin "2") (pinfunction "2_2") (pintype "passive"))
      (node (ref "R203") (pin "2") (pinfunction "2_2") (pintype "passive"))
      (node (ref "R204") (pin "1") (pinfunction "1_1") (pintype "passive"))
      (node (ref "T3") (pin "P$1") (pinfunction "6_P$1") (pintype "passive"))
    )
    (net (code "161") (name "Net-(USBB-S1)") (class "Default")
      (node (ref "R117") (pin "1") (pinfunction "1_1") (pintype "passive"))
      (node (ref "USB") (pin "M1") (pinfunction "S1_M1") (pintype "passive"))
      (node (ref "USB") (pin "M2") (pinfunction "S2_M2") (pintype "passive"))
      (node (ref "USB") (pin "M3") (pinfunction "S3_M3") (pintype "passive"))
      (node (ref "USB") (pin "M4") (pinfunction "S4_M4") (pintype "passive"))
    )
    (net (code "162") (name "Net-(Z2-PadA)") (class "Default")
      (node (ref "Z2") (pin "A") (pinfunction "A_A") (pintype "passive"))
      (node (ref "Z3") (pin "C") (pinfunction "C_C") (pintype "passive"))
    )
    (net (code "163") (name "PWM0") (class "Default")
      (node (ref "JP3") (pin "14") (pinfunction "14_14") (pintype "passive"))
      (node (ref "MCU") (pin "65") (pinfunction "PC17/PWM-PWMH[0]/SPI0-NPCS[2]/EBI-RAS/IISC-ISDO/USART3-TXD_65") (pintype "bidirectional"))
      (node (ref "TP2") (pin "TP") (pinfunction "PP_TP") (pintype "input"))
    )
    (net (code "164") (name "PWM1") (class "Default")
      (node (ref "JP3") (pin "12") (pinfunction "12_12") (pintype "passive"))
      (node (ref "MCU") (pin "63") (pinfunction "PC15/PWM-PWMH[1]/SPI0-NPCS[0]/EBI-SDWE/USART0-RXD/CANIF-RXLINE[1]_63") (pintype "bidirectional"))
      (node (ref "TP1") (pin "TP") (pinfunction "PP_TP") (pintype "input"))
    )
    (net (code "165") (name "RXSW") (class "Default")
      (node (ref "JP3") (pin "10") (pinfunction "10_10") (pintype "passive"))
      (node (ref "MCU") (pin "12") (pinfunction "ADCIN2/AC1AP1/PEVC-PAD_EVT[2]/PA06_12") (pintype "bidirectional"))
      (node (ref "TP4") (pin "TP") (pinfunction "PP_TP") (pintype "input"))
    )
    (net (code "166") (name "SCK_0") (class "Default")
      (node (ref "MCU") (pin "76") (pinfunction "PD02/SPI0-SCK/TC0-CLK2/EBI-DATA[15]/QDEC0-QEPA_76") (pintype "bidirectional"))
      (node (ref "SCK0") (pin "TP") (pinfunction "PP_TP") (pintype "input"))
      (node (ref "SD") (pin "CLK") (pinfunction "CLK_CLK") (pintype "input"))
    )
    (net (code "167") (name "SCK_1") (class "Default")
      (node (ref "ADC") (pin "9") (pinfunction "SCK_9") (pintype "input"))
      (node (ref "DDS") (pin "48") (pinfunction "SCK_48") (pintype "input"))
      (node (ref "JP5") (pin "2") (pinfunction "2_2") (pintype "passive"))
      (node (ref "MCU") (pin "44") (pinfunction "MACB-RXD[2]/TC0-CLK1/SPI1-SCK/IISC-IMCK/AC1FA1-ACBOUT/PB21_44") (pintype "bidirectional"))
    )
    (net (code "168") (name "SDSW") (class "Default")
      (node (ref "MCU") (pin "81") (pinfunction "PD10/USART1-RI/CANIF-TXLINE[0]/EBI-ADDR[7]/QDEC0-QEPB/USART4-RTS_81") (pintype "bidirectional"))
      (node (ref "R119") (pin "2") (pinfunction "2_2") (pintype "passive"))
      (node (ref "SD") (pin "SWB") (pinfunction "SWB_SWB") (pintype "passive"))
    )
    (net (code "169") (name "TPA") (class "Default")
      (node (ref "JP3") (pin "6") (pinfunction "6_6") (pintype "passive"))
      (node (ref "MCU") (pin "14") (pinfunction "ADCIN4/AC1BP1/EIC-EXTINT[2]/PA08_14") (pintype "bidirectional"))
      (node (ref "TP5") (pin "TP") (pinfunction "PP_TP") (pintype "input"))
    )
    (net (code "170") (name "TXSW") (class "Default")
      (node (ref "JP3") (pin "8") (pinfunction "8_8") (pintype "passive"))
      (node (ref "MCU") (pin "13") (pinfunction "ADCIN3/AC1AN1/PEVC-PAD_EVT[3]/PA07_13") (pintype "bidirectional"))
      (node (ref "TP3") (pin "TP") (pinfunction "PP_TP") (pintype "input"))
    )
    (net (code "171") (name "USART1_CTS") (class "Default")
      (node (ref "FTDI") (pin "3") (pinfunction "RTS#_3") (pintype "output"))
      (node (ref "MCU") (pin "86") (pinfunction "PD13/USART1-CTS/USART1-CLK/EBI-SDCK/PEVC-PAD_EVT[8]/MACB-RXD[0]_86") (pintype "bidirectional"))
    )
    (net (code "172") (name "USART1_RTS") (class "Default")
      (node (ref "FTDI") (pin "11") (pinfunction "CTS#_11") (pintype "input"))
      (node (ref "MCU") (pin "87") (pinfunction "PD14/USART1-RTS/EIC-EXTINT[7]/EBI-ADDR[10]/PEVC-PAD_EVT[9]/MACB-RXD[1]_87") (pintype "bidirectional"))
    )
    (net (code "173") (name "USART1_RXD") (class "Default")
      (node (ref "FTDI") (pin "1") (pinfunction "TXD_1") (pintype "output"))
      (node (ref "MCU") (pin "85") (pinfunction "PD12/USART1-RXD/USB-VBOF/EBI-ADDR[9]/PEVC-PAD_EVT[7]/MACB-RXD[1]_85") (pintype "bidirectional"))
    )
    (net (code "174") (name "USART1_TXD") (class "Default")
      (node (ref "FTDI") (pin "5") (pinfunction "RXD_5") (pintype "input"))
      (node (ref "MCU") (pin "84") (pinfunction "PD11/USART1-TXD/USB-ID/EBI-ADDR[8]/PEVC-PAD_EVT[6]/MACB-TXD[0]_84") (pintype "bidirectional"))
    )
    (net (code "175") (name "VDDANA") (class "Default")
      (node (ref "CB107") (pin "1") (pinfunction "1_1") (pintype "passive"))
      (node (ref "CB108") (pin "1") (pinfunction "1_1") (pintype "passive"))
      (node (ref "FB3") (pin "1") (pinfunction "1_1") (pintype "passive"))
      (node (ref "MCU") (pin "27") (pinfunction "VDDANA_27") (pintype "power_in"))
      (node (ref "R118") (pin "1") (pinfunction "1_1") (pintype "passive"))
    )
    (net (code "176") (name "VREF") (class "Default")
      (node (ref "ADC") (pin "3") (pinfunction "VREF_3") (pintype "passive"))
      (node (ref "CB302") (pin "1") (pinfunction "1_1") (pintype "passive"))
      (node (ref "CB303") (pin "1") (pinfunction "1_1") (pintype "passive"))
      (node (ref "CB304") (pin "1") (pinfunction "1_1") (pintype "passive"))
      (node (ref "R322") (pin "2") (pinfunction "2_2") (pintype "passive"))
      (node (ref "REF1") (pin "5") (pinfunction "OUT_S_5") (pintype "passive"))
      (node (ref "REF1") (pin "6") (pinfunction "OUT_F_6") (pintype "output"))
    )
    (net (code "177") (name "VREF{slash}2") (class "Default")
      (node (ref "OP4") (pin "1") (pinfunction "OUT_1") (pintype "output"))
      (node (ref "OP4") (pin "4") (pinfunction "-IN_4") (pintype "input"))
      (node (ref "R308") (pin "2") (pinfunction "2_2") (pintype "passive"))
      (node (ref "R318") (pin "2") (pinfunction "2_2") (pintype "passive"))
      (node (ref "R321") (pin "2") (pinfunction "2_2") (pintype "passive"))
      (node (ref "R324") (pin "2") (pinfunction "2_2") (pintype "passive"))
    )
    (net (code "178") (name "VREF{slash}4") (class "Default")
      (node (ref "CB310") (pin "1") (pinfunction "1_1") (pintype "passive"))
      (node (ref "OP3") (pin "12") (pinfunction "+IN_12") (pintype "input"))
      (node (ref "OP3") (pin "3") (pinfunction "+IN_3") (pintype "input"))
      (node (ref "R324") (pin "1") (pinfunction "1_1") (pintype "passive"))
      (node (ref "R325") (pin "1") (pinfunction "1_1") (pintype "passive"))
    )
    (net (code "179") (name "unconnected-(DDSA-SYNC_IN-Pad1)") (class "Default")
      (node (ref "DDS") (pin "1") (pinfunction "SYNC_IN_1") (pintype "input"))
    )
    (net (code "180") (name "unconnected-(DDSA-SYNC_OUT-Pad2)") (class "Default")
      (node (ref "DDS") (pin "2") (pinfunction "SYNC_OUT_2") (pintype "output"))
    )
    (net (code "181") (name "unconnected-(DDSD-SDIO1-Pad51)") (class "Default")
      (node (ref "DDS") (pin "51") (pinfunction "SDIO1_51") (pintype "bidirectional"))
    )
    (net (code "182") (name "unconnected-(FTDI-CBUS2-Pad13)") (class "Default")
      (node (ref "FTDI") (pin "13") (pinfunction "CBUS2_13") (pintype "bidirectional"))
    )
    (net (code "183") (name "unconnected-(FTDI-CBUS3-Pad14)") (class "Default")
      (node (ref "FTDI") (pin "14") (pinfunction "CBUS3_14") (pintype "bidirectional"))
    )
    (net (code "184") (name "unconnected-(FTDI-CBUS4-Pad12)") (class "Default")
      (node (ref "FTDI") (pin "12") (pinfunction "CBUS4_12") (pintype "bidirectional"))
    )
    (net (code "185") (name "unconnected-(FTDI-DCD#-Pad10)") (class "Default")
      (node (ref "FTDI") (pin "10") (pinfunction "DCD#_10") (pintype "input"))
    )
    (net (code "186") (name "unconnected-(FTDI-DSR#-Pad9)") (class "Default")
      (node (ref "FTDI") (pin "9") (pinfunction "DSR#_9") (pintype "input"))
    )
    (net (code "187") (name "unconnected-(FTDI-DTR#-Pad2)") (class "Default")
      (node (ref "FTDI") (pin "2") (pinfunction "DTR#_2") (pintype "output"))
    )
    (net (code "188") (name "unconnected-(FTDI-OSCI-Pad27)") (class "Default")
      (node (ref "FTDI") (pin "27") (pinfunction "OSCI_27") (pintype "input"))
    )
    (net (code "189") (name "unconnected-(FTDI-OSCO-Pad28)") (class "Default")
      (node (ref "FTDI") (pin "28") (pinfunction "OSCO_28") (pintype "output"))
    )
    (net (code "190") (name "unconnected-(FTDI-RI#-Pad6)") (class "Default")
      (node (ref "FTDI") (pin "6") (pinfunction "RI#_6") (pintype "input"))
    )
    (net (code "191") (name "unconnected-(JTAG-Pad7)") (class "Default")
      (node (ref "JTAG") (pin "7") (pinfunction "7_7") (pintype "passive"))
    )
    (net (code "192") (name "unconnected-(JTAG-Pad8)") (class "Default")
      (node (ref "JTAG") (pin "8") (pinfunction "8_8") (pintype "passive"))
    )
    (net (code "193") (name "unconnected-(MCU-AC1BN0{slash}SPI1-NPCS[1]{slash}DAC1B{slash}PA15-Pad21)") (class "Default")
      (node (ref "MCU") (pin "21") (pinfunction "AC1BN0/SPI1-NPCS[1]/DAC1B/PA15_21") (pintype "bidirectional"))
    )
    (net (code "194") (name "unconnected-(MCU-AC1BP0{slash}SPI1-NPCS[0]{slash}PA14-Pad20)") (class "Default")
      (node (ref "MCU") (pin "20") (pinfunction "AC1BP0/SPI1-NPCS[0]/PA14_20") (pintype "bidirectional"))
    )
    (net (code "195") (name "unconnected-(MCU-ADCIN0{slash}USB-ID{slash}ACIFA0-ACAOUT{slash}PA04-Pad10)") (class "Default")
      (node (ref "MCU") (pin "10") (pinfunction "ADCIN0/USB-ID/ACIFA0-ACAOUT/PA04_10") (pintype "bidirectional"))
    )
    (net (code "196") (name "unconnected-(MCU-ADCIN1{slash}USB-VBOF{slash}ACIFA0-ACBOUT{slash}PA05-Pad11)") (class "Default")
      (node (ref "MCU") (pin "11") (pinfunction "ADCIN1/USB-VBOF/ACIFA0-ACBOUT/PA05_11") (pintype "bidirectional"))
    )
    (net (code "197") (name "unconnected-(MCU-ADCIN8{slash}EIC-EXTINT[1]{slash}PA19-Pad25)") (class "Default")
      (node (ref "MCU") (pin "25") (pinfunction "ADCIN8/EIC-EXTINT[1]/PA19_25") (pintype "bidirectional"))
    )
    (net (code "198") (name "unconnected-(MCU-ADCIN10{slash}AC0BN0{slash}DAC0B{slash}PA21-Pad29)") (class "Default")
      (node (ref "MCU") (pin "29") (pinfunction "ADCIN10/AC0BN0/DAC0B/PA21_29") (pintype "bidirectional"))
    )
    (net (code "199") (name "unconnected-(MCU-ADCIN13{slash}SPI1-NCS[2]{slash}PA24-Pad32)") (class "Default")
      (node (ref "MCU") (pin "32") (pinfunction "ADCIN13/SPI1-NCS[2]/PA24_32") (pintype "bidirectional"))
    )
    (net (code "200") (name "unconnected-(MCU-ADCIN14{slash}SPI1-NPCS[3]{slash}EIC-EXTINT[0]{slash}PA25-Pad33)") (class "Default")
      (node (ref "MCU") (pin "33") (pinfunction "ADCIN14/SPI1-NPCS[3]/EIC-EXTINT[0]/PA25_33") (pintype "bidirectional"))
    )
    (net (code "201") (name "unconnected-(MCU-CANIF-TXLINE[1]{slash}PEVC-PAD_EVT[11]{slash}XOUT32{slash}PB01-Pad97)") (class "Default")
      (node (ref "MCU") (pin "97") (pinfunction "CANIF-TXLINE[1]/PEVC-PAD_EVT[11]/XOUT32/PB01_97") (pintype "bidirectional"))
    )
    (net (code "202") (name "unconnected-(MCU-MACB-SPEED{slash}ADCIN11{slash}AC0AN0{slash}PEVC-PAD_EVT[4]{slash}PA22-Pad30)") (class "Default")
      (node (ref "MCU") (pin "30") (pinfunction "MACB-SPEED/ADCIN11/AC0AN0/PEVC-PAD_EVT[4]/PA22_30") (pintype "bidirectional"))
    )
    (net (code "203") (name "unconnected-(MCU-MACB-TXD[2]SPI1-MOSI{slash}CANIF-RXLINE[0]{slash}QDEC1-QEPI{slash}PB04-Pad7)") (class "Default")
      (node (ref "MCU") (pin "7") (pinfunction "MACB-TXD[2]SPI1-MOSI/CANIF-RXLINE[0]/QDEC1-QEPI/PB04_7") (pintype "bidirectional"))
    )
    (net (code "204") (name "unconnected-(MCU-MACB-TXD[3]{slash}SPI1-MISO{slash}CANIF-TXLINE[0]{slash}PEVC-PAD_EVT[12]{slash}USART3-CLK{slash}PB05-Pad8)") (class "Default")
      (node (ref "MCU") (pin "8") (pinfunction "MACB-TXD[3]/SPI1-MISO/CANIF-TXLINE[0]/PEVC-PAD_EVT[12]/USART3-CLK/PB05_8") (pintype "bidirectional"))
    )
    (net (code "205") (name "unconnected-(MCU-MACB-TX_ER{slash}SPI1-SCK{slash}QDEC1-QEPA{slash}USART1-CLK{slash}PB06-Pad9)") (class "Default")
      (node (ref "MCU") (pin "9") (pinfunction "MACB-TX_ER/SPI1-SCK/QDEC1-QEPA/USART1-CLK/PB06_9") (pintype "bidirectional"))
    )
    (net (code "206") (name "unconnected-(MCU-MACB-WOL{slash}ADCIN12{slash}AC0BP0{slash}PEVC-PAD_EVT[5]{slash}PA23-Pad31)") (class "Default")
      (node (ref "MCU") (pin "31") (pinfunction "MACB-WOL/ADCIN12/AC0BP0/PEVC-PAD_EVT[5]/PA23_31") (pintype "bidirectional"))
    )
    (net (code "207") (name "unconnected-(MCU-PC04{slash}TWIMS1-TWD{slash}EIC-EXTINT[3]{slash}USART2-TXD{slash}TC0-B1-Pad55)") (class "Default")
      (node (ref "MCU") (pin "55") (pinfunction "PC04/TWIMS1-TWD/EIC-EXTINT[3]/USART2-TXD/TC0-B1_55") (pintype "bidirectional"))
    )
    (net (code "208") (name "unconnected-(MCU-PC05{slash}TWIMS1-TWCK{slash}EIC-EXTINT[4]{slash}USART2-RXD{slash}TC0-A2-Pad56)") (class "Default")
      (node (ref "MCU") (pin "56") (pinfunction "PC05/TWIMS1-TWCK/EIC-EXTINT[4]/USART2-RXD/TC0-A2_56") (pintype "bidirectional"))
    )
    (net (code "209") (name "unconnected-(MCU-PC07{slash}PEVC_EVT[2]_{slash}EBI_NCS[3]{slash}USART2-RTS{slash}TC0-B2{slash}TWIMS2-TWCK{slash}TWIMS1-TWALM-Pad58)") (class "Default")
      (node (ref "MCU") (pin "58") (pinfunction "PC07/PEVC_EVT[2]_/EBI_NCS[3]/USART2-RTS/TC0-B2/TWIMS2-TWCK/TWIMS1-TWALM_58") (pintype "bidirectional"))
    )
    (net (code "210") (name "unconnected-(MCU-PC11{slash}PWM-PWMH[3]{slash}CANIF-RXLINE[1]{slash}EBI-ADDR[21]{slash}TC0-CLK0-Pad59)") (class "Default")
      (node (ref "MCU") (pin "59") (pinfunction "PC11/PWM-PWMH[3]/CANIF-RXLINE[1]/EBI-ADDR[21]/TC0-CLK0_59") (pintype "bidirectional"))
    )
    (net (code "211") (name "unconnected-(MCU-PC12{slash}PWM-PWML[3]{slash}CANIF-TXLINE[1]{slash}EBI-ADDR[20]{slash}USART2-CLK-Pad60)") (class "Default")
      (node (ref "MCU") (pin "60") (pinfunction "PC12/PWM-PWML[3]/CANIF-TXLINE[1]/EBI-ADDR[20]/USART2-CLK_60") (pintype "bidirectional"))
    )
    (net (code "212") (name "unconnected-(MCU-PC16{slash}PWM-PWML[1]{slash}SPI0-NPCS[1]{slash}EBI-CAS{slash}USART0-TXD{slash}CANIF-TXLINE[1]-Pad64)") (class "Default")
      (node (ref "MCU") (pin "64") (pinfunction "PC16/PWM-PWML[1]/SPI0-NPCS[1]/EBI-CAS/USART0-TXD/CANIF-TXLINE[1]_64") (pintype "bidirectional"))
    )
    (net (code "213") (name "unconnected-(MCU-PC18{slash}PWM-PWML[0]{slash}EIC-EXTINT[5]{slash}EBI-SDA10{slash}IISC-ISDI{slash}USART3-RXD-Pad66)") (class "Default")
      (node (ref "MCU") (pin "66") (pinfunction "PC18/PWM-PWML[0]/EIC-EXTINT[5]/EBI-SDA10/IISC-ISDI/USART3-RXD_66") (pintype "bidirectional"))
    )
    (net (code "214") (name "unconnected-(MCU-PC21{slash}PWM-EXT_FAULTS[0]{slash}CCANIF-RXLINE[0]{slash}EBI-DATA[2]{slash}IISC-IWS-Pad69)") (class "Default")
      (node (ref "MCU") (pin "69") (pinfunction "PC21/PWM-EXT_FAULTS[0]/CCANIF-RXLINE[0]/EBI-DATA[2]/IISC-IWS_69") (pintype "bidirectional"))
    )
    (net (code "215") (name "unconnected-(MCU-PC22{slash}PWM-EXT_FAULTS[1]{slash}CCANIF-TXLINE[3]{slash}EBI-DATA[2]{slash}USART3-CLK-Pad70)") (class "Default")
      (node (ref "MCU") (pin "70") (pinfunction "PC22/PWM-EXT_FAULTS[1]/CCANIF-TXLINE[3]/EBI-DATA[2]/USART3-CLK_70") (pintype "bidirectional"))
    )
    (net (code "216") (name "unconnected-(MCU-PC23{slash}QDEC1-QEPB{slash}CANIF-RXLINE[1]{slash}EBI-DATA[4]{slash}PEVC-PAD_EVT[3]-Pad71)") (class "Default")
      (node (ref "MCU") (pin "71") (pinfunction "PC23/QDEC1-QEPB/CANIF-RXLINE[1]/EBI-DATA[4]/PEVC-PAD_EVT[3]_71") (pintype "bidirectional"))
    )
    (net (code "217") (name "unconnected-(MCU-PC24{slash}QDEC1-QEPA{slash}CANIF-TXLINE[1]{slash}EBI-DATA[5]{slash}PEVC-PAD_EVT[4]-Pad72)") (class "Default")
      (node (ref "MCU") (pin "72") (pinfunction "PC24/QDEC1-QEPA/CANIF-TXLINE[1]/EBI-DATA[5]/PEVC-PAD_EVT[4]_72") (pintype "bidirectional"))
    )
    (net (code "218") (name "unconnected-(MCU-PC31{slash}SPI1-NPCS[3]{slash}TC1-B0{slash}EBI-DATA[12]{slash}PEVC-PAD_EVT[5]{slash}USART4-CLK-Pad73)") (class "Default")
      (node (ref "MCU") (pin "73") (pinfunction "PC31/SPI1-NPCS[3]/TC1-B0/EBI-DATA[12]/PEVC-PAD_EVT[5]/USART4-CLK_73") (pintype "bidirectional"))
    )
    (net (code "219") (name "unconnected-(MCU-PD07{slash}USART1-DTR{slash}EIC-EXTINT[5]{slash}EBI-ADDR[4]{slash}QDEC0-QEPI{slash}USART4-TXD-Pad78)") (class "Default")
      (node (ref "MCU") (pin "78") (pinfunction "PD07/USART1-DTR/EIC-EXTINT[5]/EBI-ADDR[4]/QDEC0-QEPI/USART4-TXD_78") (pintype "bidirectional"))
    )
    (net (code "220") (name "unconnected-(MCU-PD08{slash}USART1-DSR{slash}EIC-EXTINT[6]{slash}EBI-ADDR[5]{slash}TC1-CLK2{slash}USART4-RXD-Pad79)") (class "Default")
      (node (ref "MCU") (pin "79") (pinfunction "PD08/USART1-DSR/EIC-EXTINT[6]/EBI-ADDR[5]/TC1-CLK2/USART4-RXD_79") (pintype "bidirectional"))
    )
    (net (code "221") (name "unconnected-(MCU-PD09{slash}USART1-DCD{slash}CANIF-RXLINE[0]{slash}EBI-ADDR[6]{slash}QDEC0-QEPA{slash}USART4-CTS-Pad80)") (class "Default")
      (node (ref "MCU") (pin "80") (pinfunction "PD09/USART1-DCD/CANIF-RXLINE[0]/EBI-ADDR[6]/QDEC0-QEPA/USART4-CTS_80") (pintype "bidirectional"))
    )
    (net (code "222") (name "unconnected-(MCU-PD21{slash}USART3-TXD{slash}EIC-EXTINT[0]{slash}EBI-ADDR[17]{slash}QDEC1-QEPI-Pad88)") (class "Default")
      (node (ref "MCU") (pin "88") (pinfunction "PD21/USART3-TXD/EIC-EXTINT[0]/EBI-ADDR[17]/QDEC1-QEPI_88") (pintype "bidirectional"))
    )
    (net (code "223") (name "unconnected-(MCU-PD22{slash}USART3-RXD{slash}TC0-A2]{slash}EBI-ADDR[18]{slash}SCIF-GCLK[0]-Pad89)") (class "Default")
      (node (ref "MCU") (pin "89") (pinfunction "PD22/USART3-RXD/TC0-A2]/EBI-ADDR[18]/SCIF-GCLK[0]_89") (pintype "bidirectional"))
    )
    (net (code "224") (name "unconnected-(MCU-PD23{slash}USART3-CTS{slash}USART3-CLK{slash}EBI-ADDR[19]{slash}QDEC1-QEPA-Pad90)") (class "Default")
      (node (ref "MCU") (pin "90") (pinfunction "PD23/USART3-CTS/USART3-CLK/EBI-ADDR[19]/QDEC1-QEPA_90") (pintype "bidirectional"))
    )
    (net (code "225") (name "unconnected-(MCU-PD24{slash}USART3-RTS{slash}EIC-EXTINT[8]{slash}EBI-NWE1{slash}QDEC1-QEPB-Pad91)") (class "Default")
      (node (ref "MCU") (pin "91") (pinfunction "PD24/USART3-RTS/EIC-EXTINT[8]/EBI-NWE1/QDEC1-QEPB_91") (pintype "bidirectional"))
    )
    (net (code "226") (name "unconnected-(MCU-PD29{slash}USART0-CTS{slash}EIC-EXTINT[6]{slash}USART0-CLK{slash}TC0-B0{slash}MACB-TX_CLK-Pad94)") (class "Default")
      (node (ref "MCU") (pin "94") (pinfunction "PD29/USART0-CTS/EIC-EXTINT[6]/USART0-CLK/TC0-B0/MACB-TX_CLK_94") (pintype "bidirectional"))
    )
    (net (code "227") (name "unconnected-(MCU-PD30{slash}USART0-RXD{slash}EIC-EXTINT[3]{slash}EBI-NWAIT{slash}TC0-A1{slash}MACB-TX_EN-Pad95)") (class "Default")
      (node (ref "MCU") (pin "95") (pinfunction "PD30/USART0-RXD/EIC-EXTINT[3]/EBI-NWAIT/TC0-A1/MACB-TX_EN_95") (pintype "bidirectional"))
    )
    (net (code "228") (name "unconnected-(MCU-USART0-CLK{slash}CANIF-RXLINE[1]{slash}EIC-EXTINT[8]{slash}PEVC-PAD_EVT[10]{slash}XIN32{slash}PB00-Pad96)") (class "Default")
      (node (ref "MCU") (pin "96") (pinfunction "USART0-CLK/CANIF-RXLINE[1]/EIC-EXTINT[8]/PEVC-PAD_EVT[10]/XIN32/PB00_96") (pintype "bidirectional"))
    )
    (net (code "229") (name "unconnected-(MCU-USB-ID{slash}PEVC-PAD_EVT[6]{slash}TC1-A1{slash}XIN1{slash}PB02-Pad99)") (class "Default")
      (node (ref "MCU") (pin "99") (pinfunction "USB-ID/PEVC-PAD_EVT[6]/TC1-A1/XIN1/PB02_99") (pintype "bidirectional"))
    )
    (net (code "230") (name "unconnected-(MCU-USB-VBOF{slash}PEVC-PAD-EVT[7]{slash}XOUT1{slash}PB03-Pad100)") (class "Default")
      (node (ref "MCU") (pin "100") (pinfunction "USB-VBOF/PEVC-PAD-EVT[7]/XOUT1/PB03_100") (pintype "bidirectional"))
    )
    (net (code "231") (name "unconnected-(MCU-XOUT0{slash}PB31-Pad48)") (class "Default")
      (node (ref "MCU") (pin "48") (pinfunction "XOUT0/PB31_48") (pintype "bidirectional"))
    )
    (net (code "232") (name "unconnected-(T3-5-PadP$2)") (class "Default")
      (node (ref "T3") (pin "P$2") (pinfunction "5_P$2") (pintype "passive"))
    )
    (net (code "233") (name "unconnected-(USB-Pad4)") (class "Default")
      (node (ref "USB") (pin "4") (pinfunction "4_4") (pintype "input"))
    )
  )
)
